# Attenuverting_LinExp_VCA-alt2.net
KiCad netlist of a schematic drawn in EAGLE
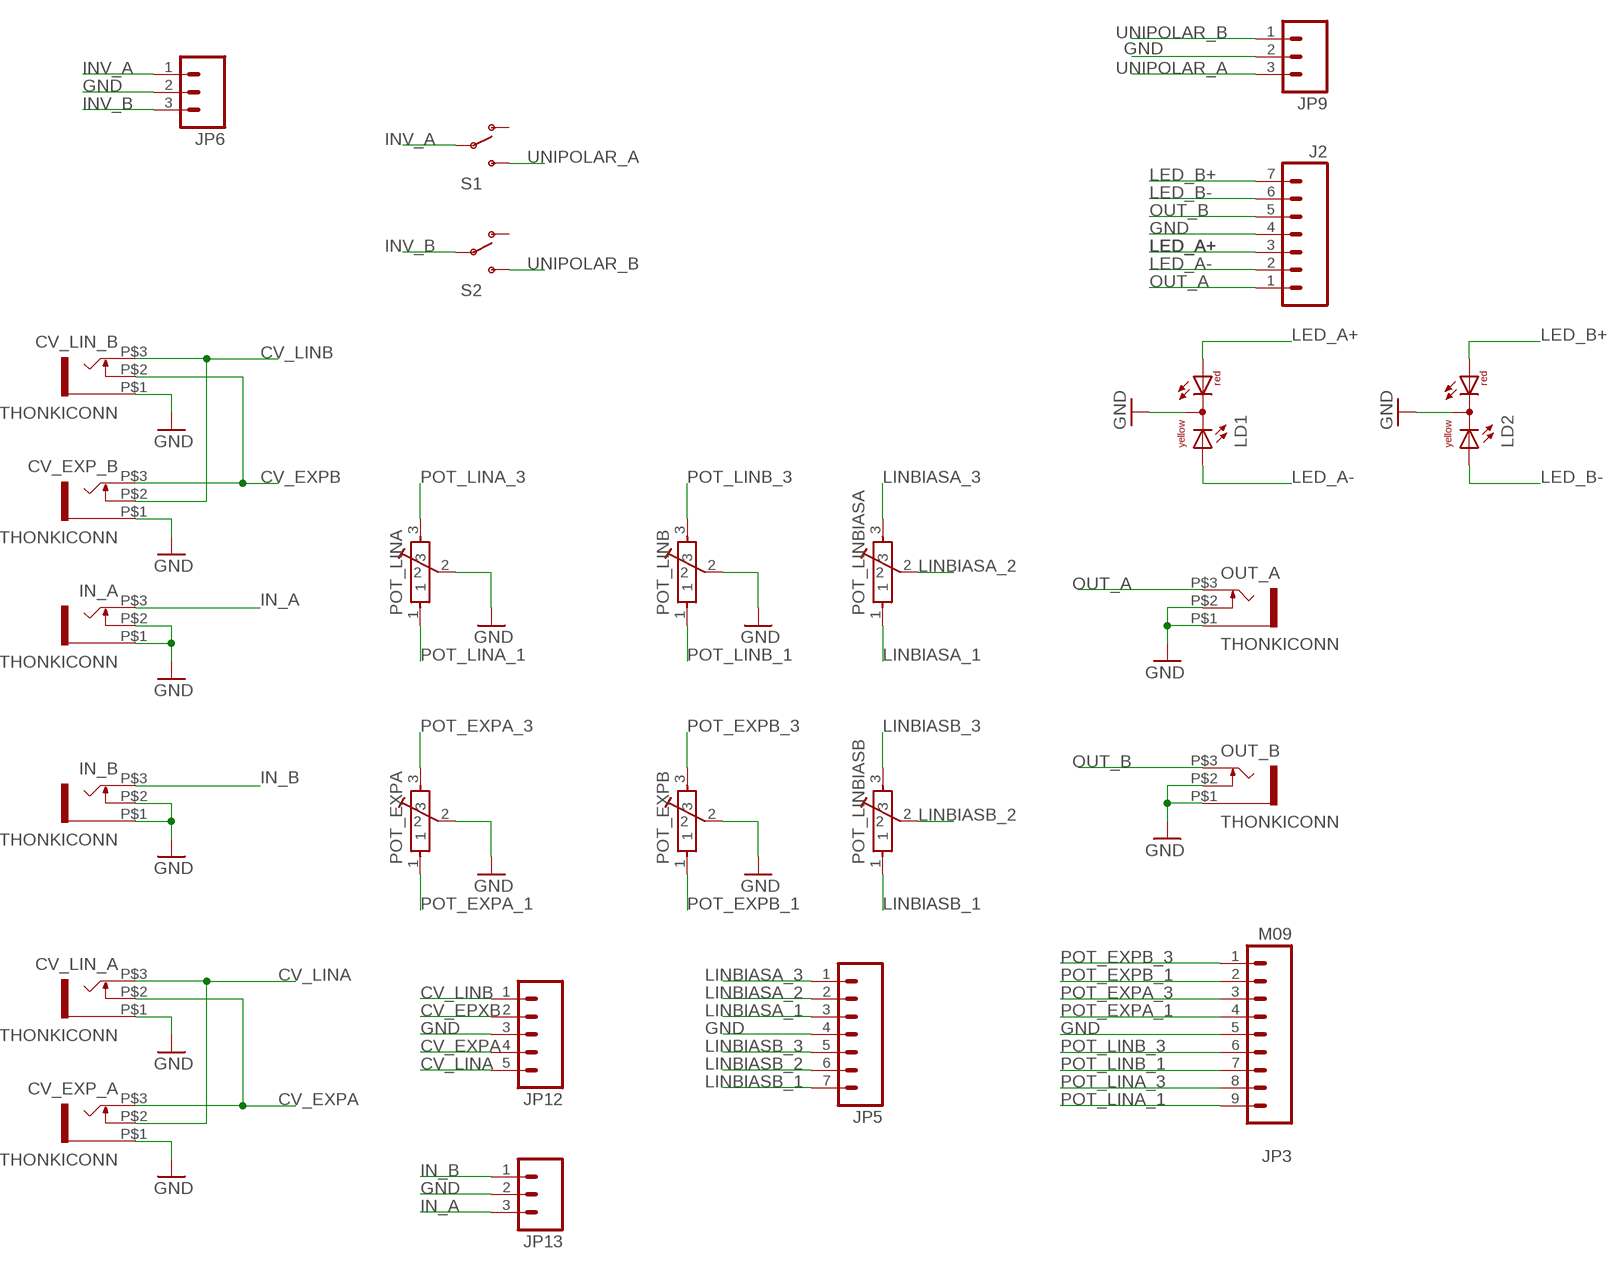
[diagram p0: schematic, sheet 1]
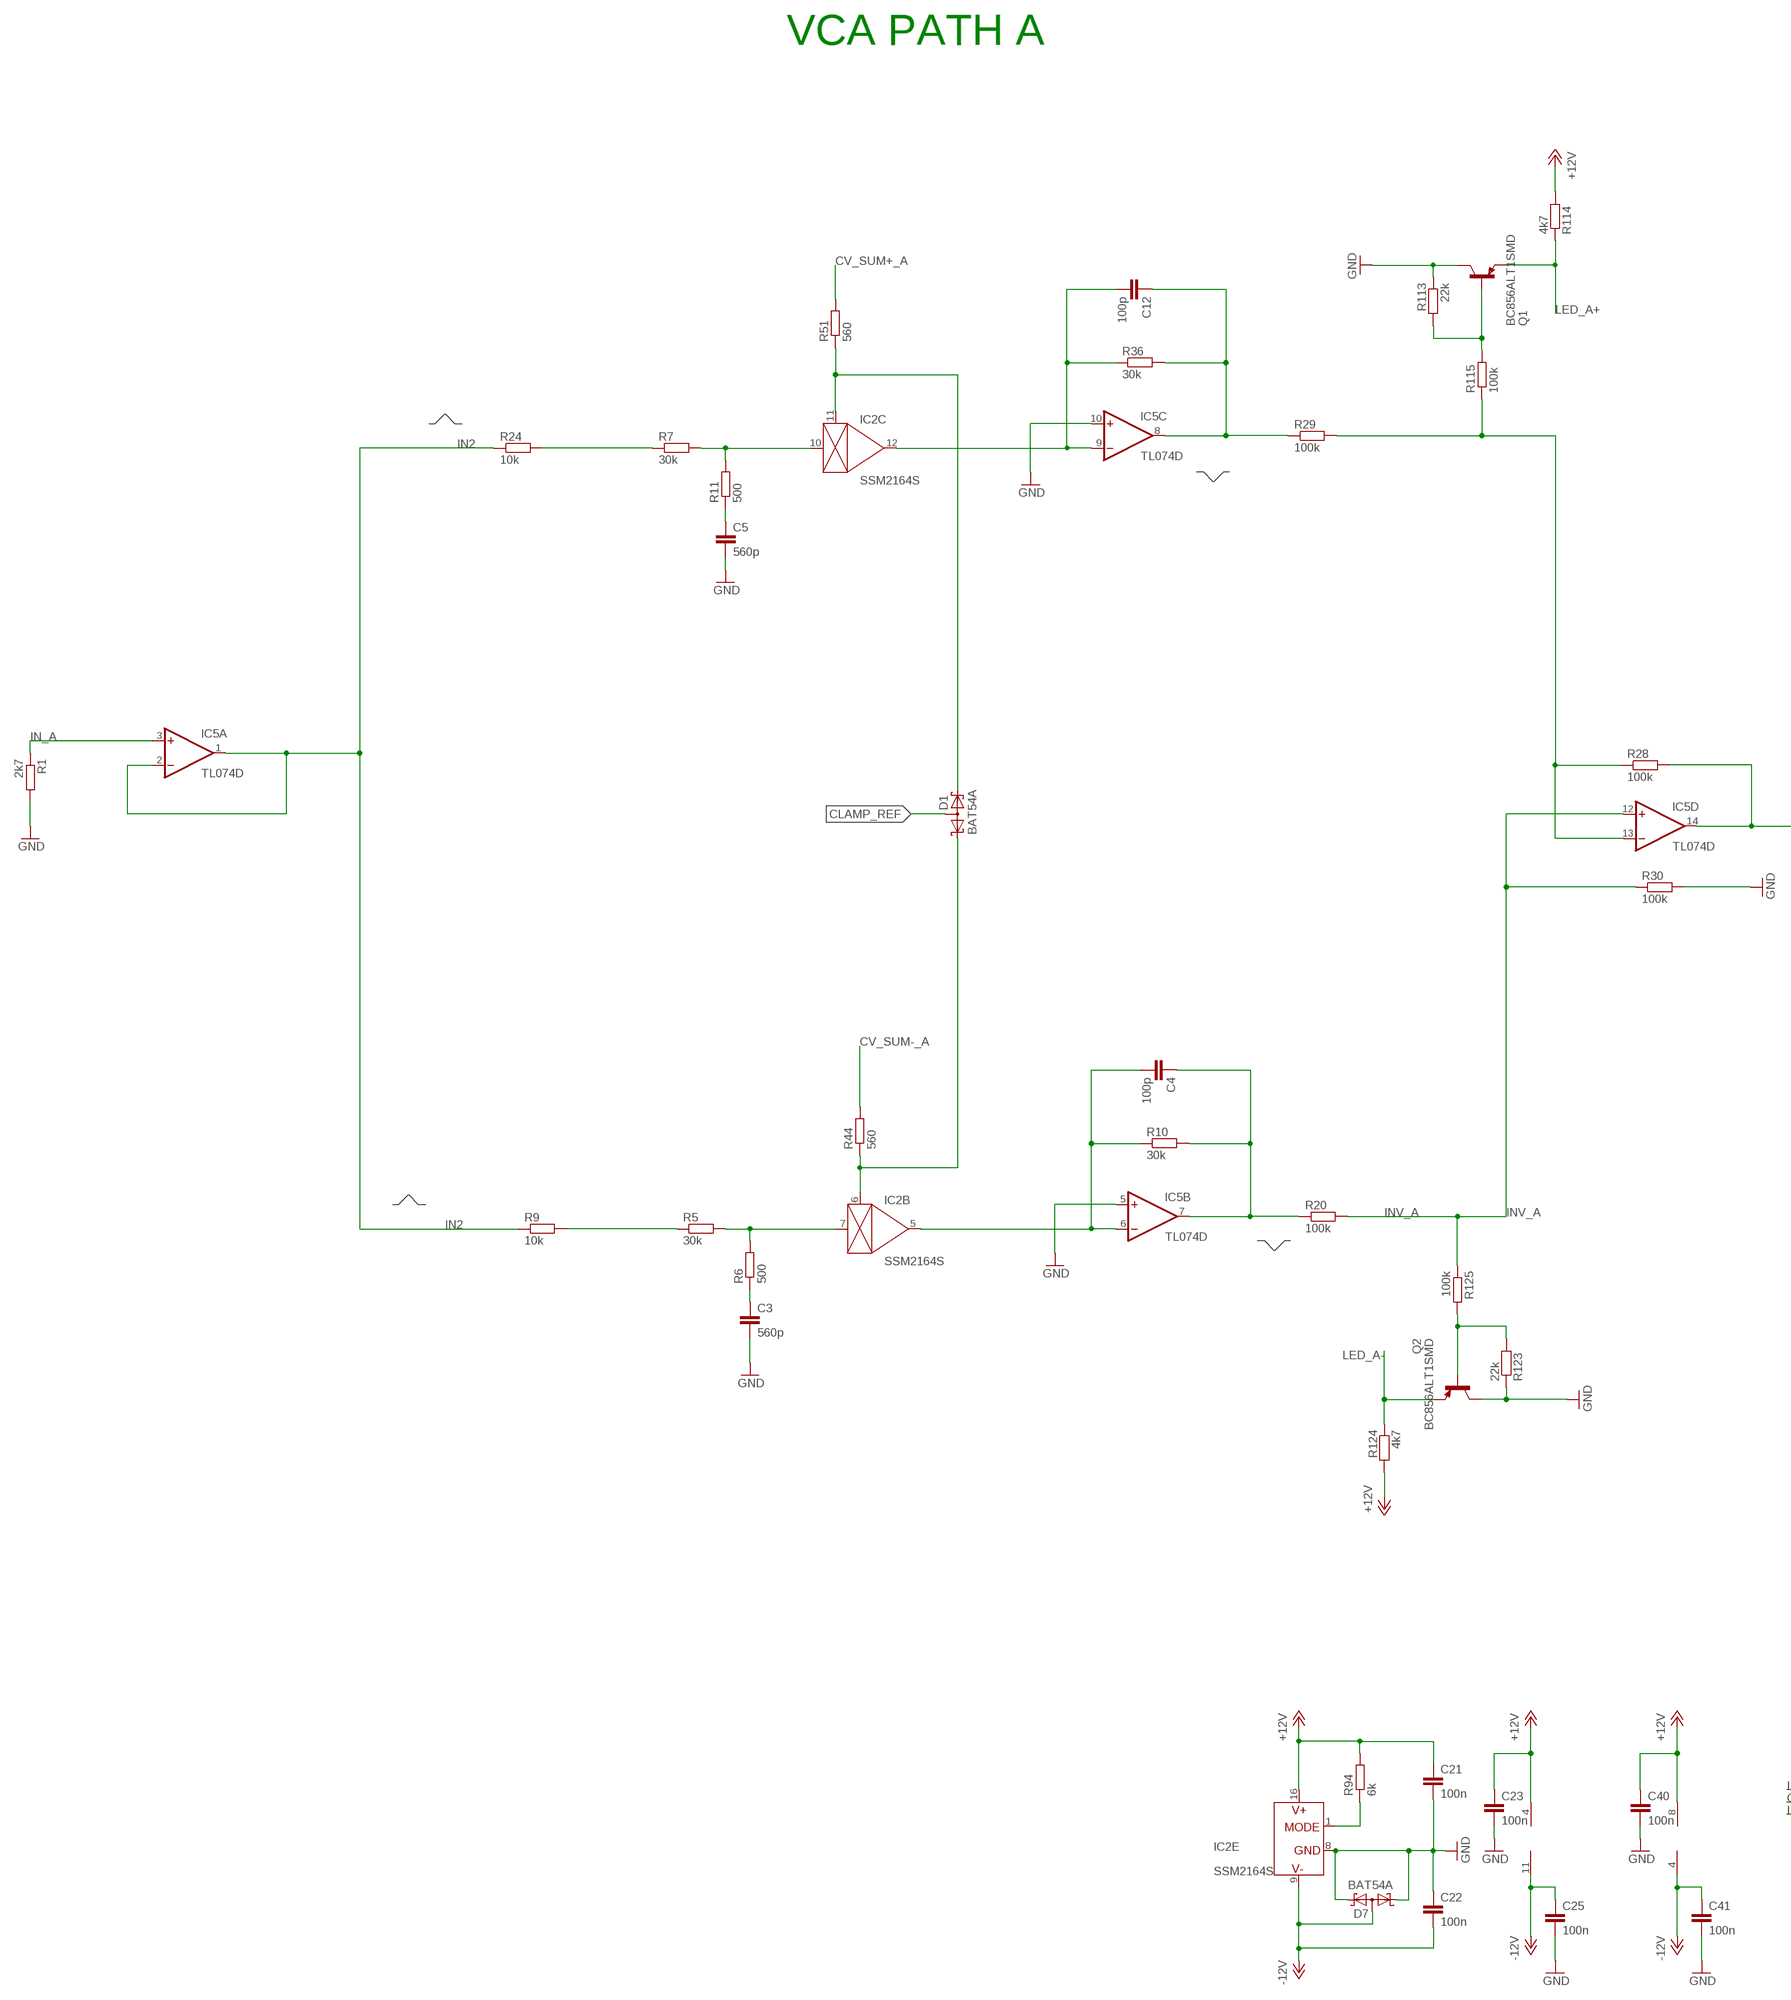
[diagram p1: schematic, sheet 2, part 1 of 2]
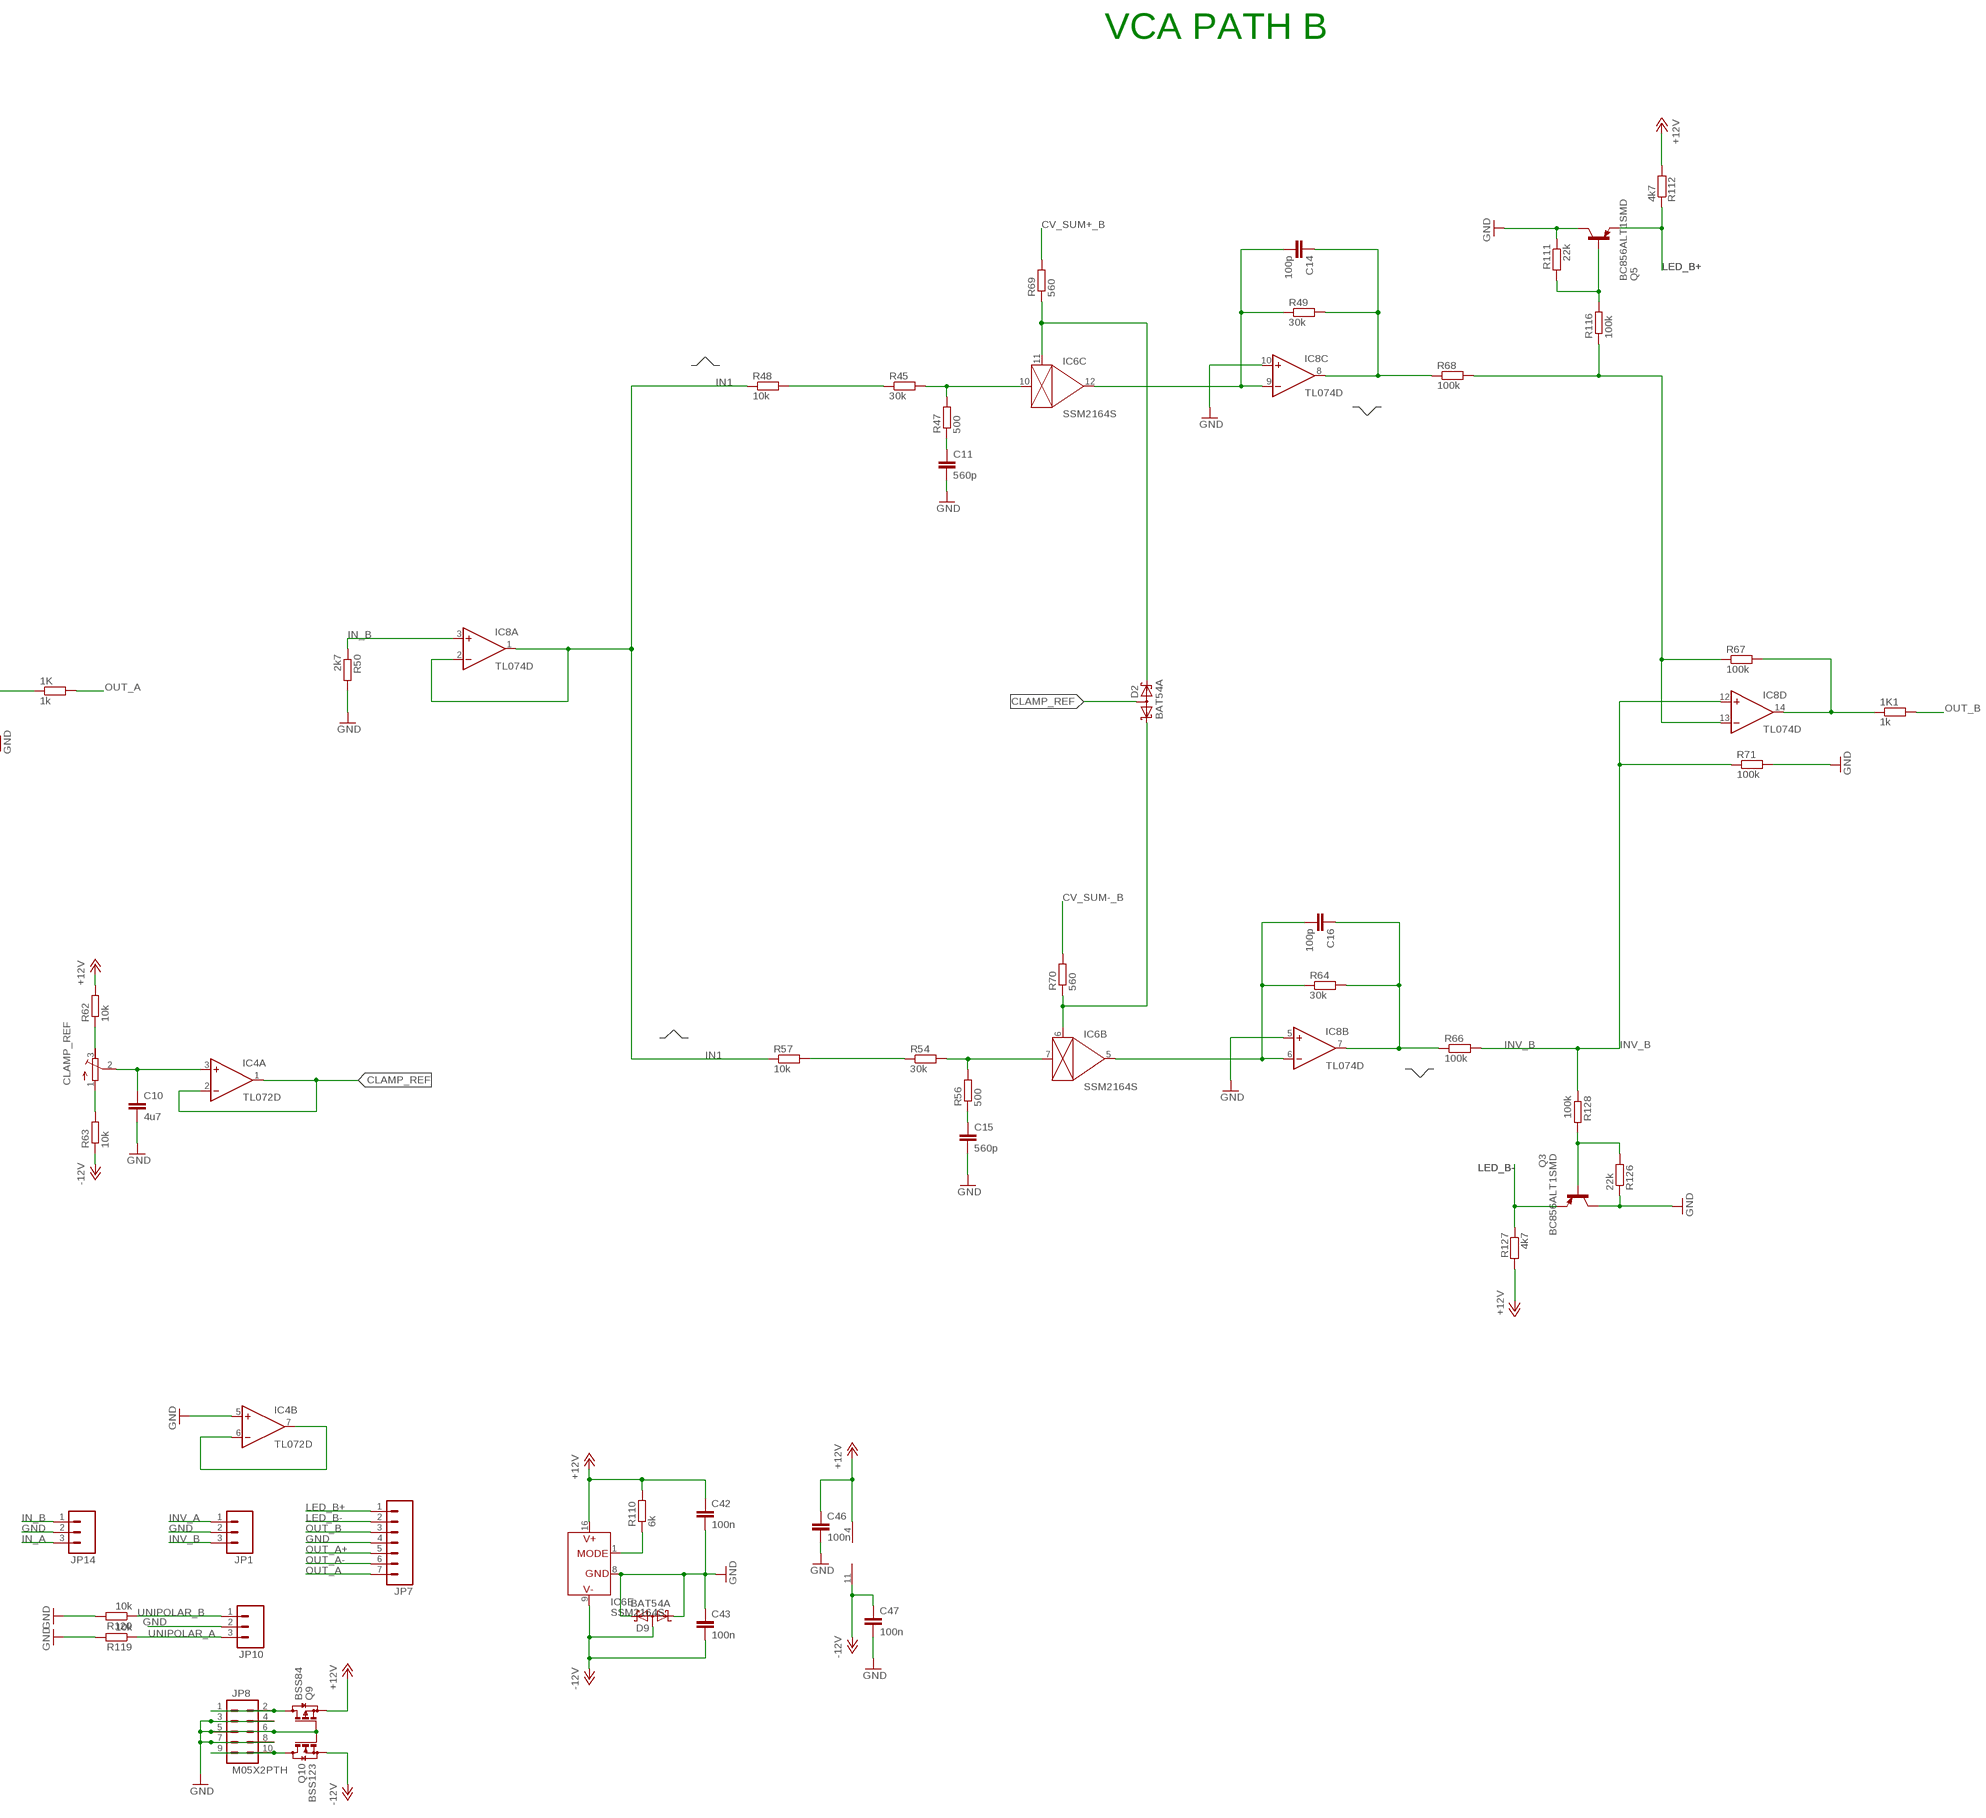
[diagram p2: schematic, sheet 2, part 2 of 2]
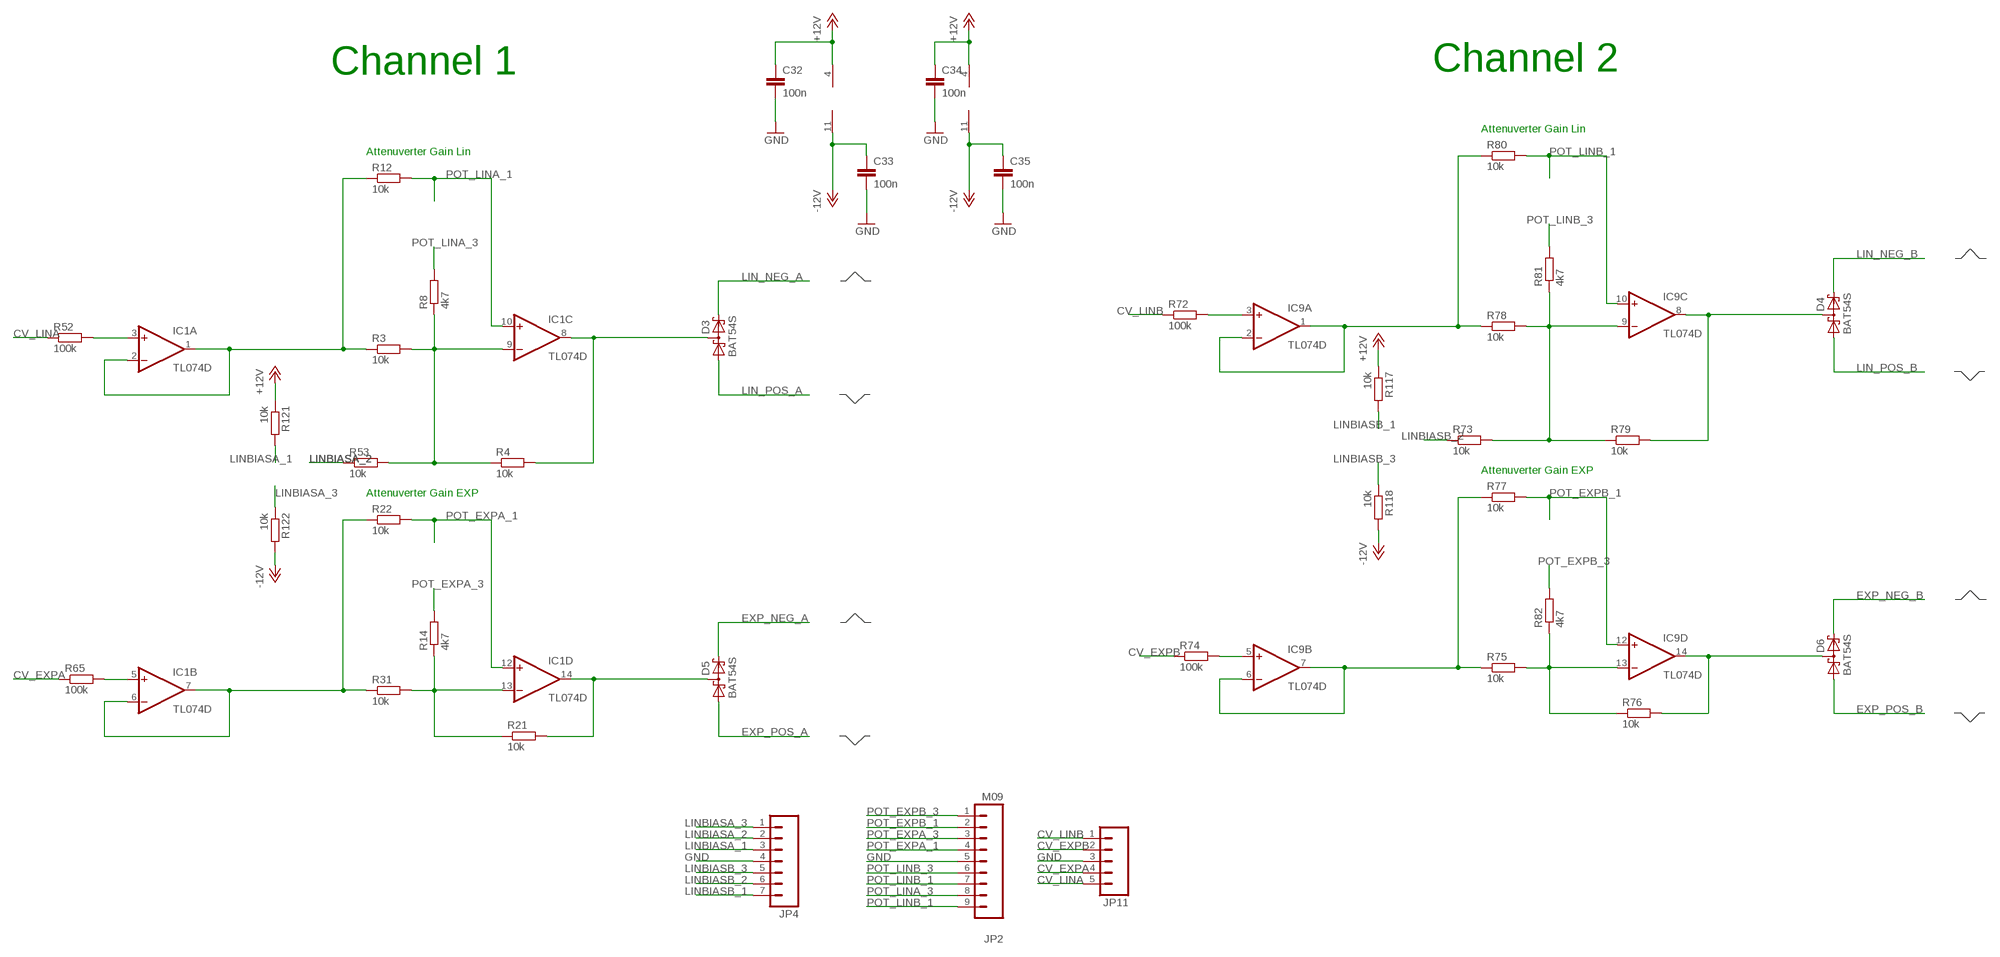
[diagram p3: schematic, sheet 3]
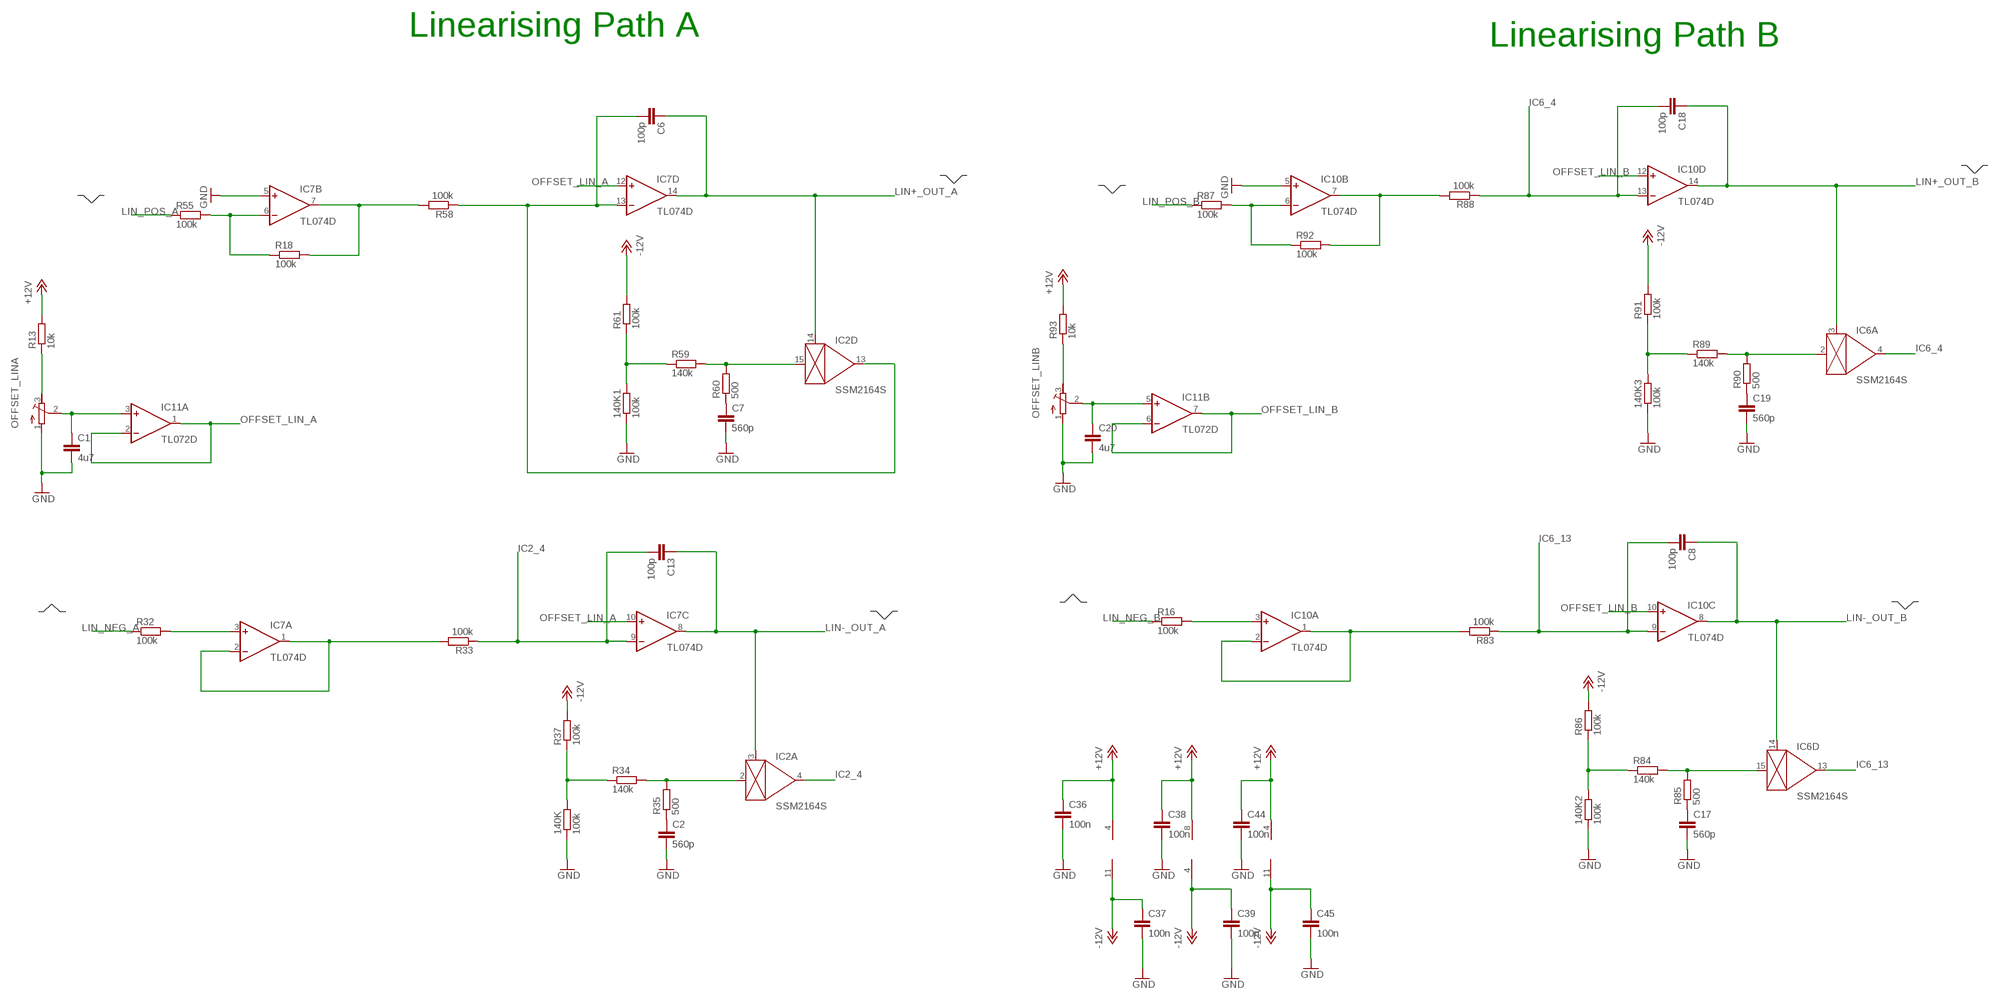
[diagram p4: schematic, sheet 4]
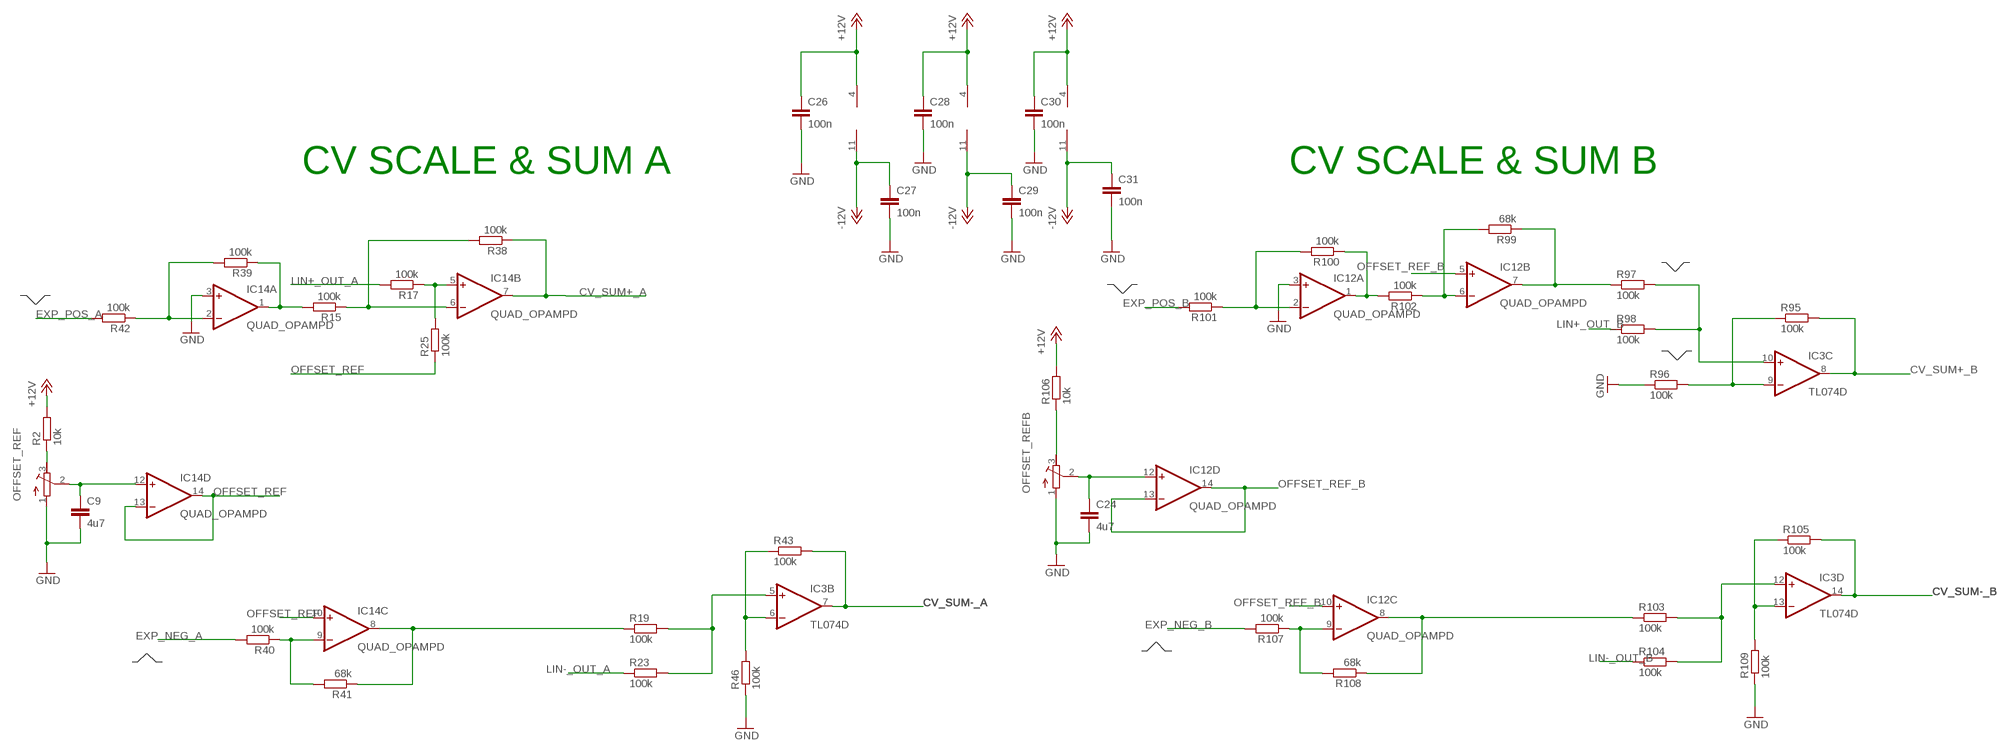
[diagram p5: schematic, sheet 5]

(export (version "E")
  (design (tool "Eeschema 10.0.6"))
  (components
    (comp (ref "140K")
      (value "100k")
      (footprint "eagle-import:0603")
      (libsource (lib "eagle-import") (part "R-EU_0603"))
    )
    (comp (ref "140K1")
      (value "100k")
      (footprint "eagle-import:0603")
      (libsource (lib "eagle-import") (part "R-EU_0603"))
    )
    (comp (ref "140K2")
      (value "100k")
      (footprint "eagle-import:0603")
      (libsource (lib "eagle-import") (part "R-EU_0603"))
    )
    (comp (ref "140K3")
      (value "100k")
      (footprint "eagle-import:0603")
      (libsource (lib "eagle-import") (part "R-EU_0603"))
    )
    (comp (ref "C1")
      (value "4u7")
      (footprint "eagle-import:C0603K")
      (libsource (lib "eagle-import") (part "resistor_C-EUC0603K"))
    )
    (comp (ref "C2")
      (value "560p")
      (footprint "eagle-import:C0603K")
      (libsource (lib "eagle-import") (part "resistor_C-EUC0603K"))
    )
    (comp (ref "C6")
      (value "100p")
      (footprint "eagle-import:C0603K")
      (libsource (lib "eagle-import") (part "resistor_C-EUC0603K"))
    )
    (comp (ref "C7")
      (value "560p")
      (footprint "eagle-import:C0603K")
      (libsource (lib "eagle-import") (part "resistor_C-EUC0603K"))
    )
    (comp (ref "C8")
      (value "100p")
      (footprint "eagle-import:C0603K")
      (libsource (lib "eagle-import") (part "resistor_C-EUC0603K"))
    )
    (comp (ref "C13")
      (value "100p")
      (footprint "eagle-import:C0603K")
      (libsource (lib "eagle-import") (part "resistor_C-EUC0603K"))
    )
    (comp (ref "C17")
      (value "560p")
      (footprint "eagle-import:C0603K")
      (libsource (lib "eagle-import") (part "resistor_C-EUC0603K"))
    )
    (comp (ref "C18")
      (value "100p")
      (footprint "eagle-import:C0603K")
      (libsource (lib "eagle-import") (part "resistor_C-EUC0603K"))
    )
    (comp (ref "C19")
      (value "560p")
      (footprint "eagle-import:C0603K")
      (libsource (lib "eagle-import") (part "resistor_C-EUC0603K"))
    )
    (comp (ref "C20")
      (value "4u7")
      (footprint "eagle-import:C0603K")
      (libsource (lib "eagle-import") (part "resistor_C-EUC0603K"))
    )
    (comp (ref "C36")
      (value "100n")
      (footprint "eagle-import:C0603K")
      (libsource (lib "eagle-import") (part "rcl@1_C-EUC0603K"))
    )
    (comp (ref "C37")
      (value "100n")
      (footprint "eagle-import:C0603K")
      (libsource (lib "eagle-import") (part "rcl@1_C-EUC0603K"))
    )
    (comp (ref "C38")
      (value "100n")
      (footprint "eagle-import:C0603K")
      (libsource (lib "eagle-import") (part "rcl@1_C-EUC0603K"))
    )
    (comp (ref "C39")
      (value "100n")
      (footprint "eagle-import:C0603K")
      (libsource (lib "eagle-import") (part "rcl@1_C-EUC0603K"))
    )
    (comp (ref "C44")
      (value "100n")
      (footprint "eagle-import:C0603K")
      (libsource (lib "eagle-import") (part "rcl@1_C-EUC0603K"))
    )
    (comp (ref "C45")
      (value "100n")
      (footprint "eagle-import:C0603K")
      (libsource (lib "eagle-import") (part "rcl@1_C-EUC0603K"))
    )
    (comp (ref "IC2")
      (value "SSM2164S")
      (footprint "eagle-import:SOIC16N")
      (fields (field (name "OC_FARNELL") "unknown"))
      (libsource (lib "eagle-import") (part "SSM2164S"))
    )
    (comp (ref "IC6")
      (value "SSM2164S")
      (footprint "eagle-import:SOIC16N")
      (fields (field (name "OC_FARNELL") "unknown"))
      (libsource (lib "eagle-import") (part "SSM2164S"))
    )
    (comp (ref "IC7")
      (value "TL074D")
      (footprint "eagle-import:SO14")
      (fields (field (name "OC_FARNELL") "unknown"))
      (libsource (lib "eagle-import") (part "TL074D"))
    )
    (comp (ref "IC10")
      (value "TL074D")
      (footprint "eagle-import:SO14")
      (fields (field (name "OC_FARNELL") "unknown"))
      (libsource (lib "eagle-import") (part "TL074D"))
    )
    (comp (ref "IC11")
      (value "TL072D")
      (footprint "eagle-import:SO08")
      (fields (field (name "OC_FARNELL") "unknown"))
      (libsource (lib "eagle-import") (part "TL072D"))
    )
    (comp (ref "OFFSET_LINA")
      (value "R-TRIMM64W")
      (footprint "eagle-import:RTRIM64W")
      (libsource (lib "eagle-import") (part "R-TRIMM64W"))
    )
    (comp (ref "OFFSET_LINB")
      (value "R-TRIMM64W")
      (footprint "eagle-import:RTRIM64W")
      (libsource (lib "eagle-import") (part "R-TRIMM64W"))
    )
    (comp (ref "R13")
      (value "10k")
      (footprint "eagle-import:0603")
      (libsource (lib "eagle-import") (part "R-EU_0603"))
    )
    (comp (ref "R16")
      (value "100k")
      (footprint "eagle-import:0603")
      (libsource (lib "eagle-import") (part "R-EU_0603"))
    )
    (comp (ref "R18")
      (value "100k")
      (footprint "eagle-import:0603")
      (libsource (lib "eagle-import") (part "R-EU_0603"))
    )
    (comp (ref "R32")
      (value "100k")
      (footprint "eagle-import:0603")
      (libsource (lib "eagle-import") (part "R-EU_0603"))
    )
    (comp (ref "R33")
      (value "100k")
      (footprint "eagle-import:0603")
      (libsource (lib "eagle-import") (part "R-EU_0603"))
    )
    (comp (ref "R34")
      (value "140k")
      (footprint "eagle-import:0603")
      (libsource (lib "eagle-import") (part "R-EU_0603"))
    )
    (comp (ref "R35")
      (value "500")
      (footprint "eagle-import:0603")
      (libsource (lib "eagle-import") (part "R-EU_0603"))
    )
    (comp (ref "R37")
      (value "100k")
      (footprint "eagle-import:0603")
      (libsource (lib "eagle-import") (part "R-EU_0603"))
    )
    (comp (ref "R55")
      (value "100k")
      (footprint "eagle-import:0603")
      (libsource (lib "eagle-import") (part "R-EU_0603"))
    )
    (comp (ref "R58")
      (value "100k")
      (footprint "eagle-import:0603")
      (libsource (lib "eagle-import") (part "R-EU_0603"))
    )
    (comp (ref "R59")
      (value "140k")
      (footprint "eagle-import:0603")
      (libsource (lib "eagle-import") (part "R-EU_0603"))
    )
    (comp (ref "R60")
      (value "500")
      (footprint "eagle-import:0603")
      (libsource (lib "eagle-import") (part "R-EU_0603"))
    )
    (comp (ref "R61")
      (value "100k")
      (footprint "eagle-import:0603")
      (libsource (lib "eagle-import") (part "R-EU_0603"))
    )
    (comp (ref "R83")
      (value "100k")
      (footprint "eagle-import:0603")
      (libsource (lib "eagle-import") (part "R-EU_0603"))
    )
    (comp (ref "R84")
      (value "140k")
      (footprint "eagle-import:0603")
      (libsource (lib "eagle-import") (part "R-EU_0603"))
    )
    (comp (ref "R85")
      (value "500")
      (footprint "eagle-import:0603")
      (libsource (lib "eagle-import") (part "R-EU_0603"))
    )
    (comp (ref "R86")
      (value "100k")
      (footprint "eagle-import:0603")
      (libsource (lib "eagle-import") (part "R-EU_0603"))
    )
    (comp (ref "R87")
      (value "100k")
      (footprint "eagle-import:0603")
      (libsource (lib "eagle-import") (part "R-EU_0603"))
    )
    (comp (ref "R88")
      (value "100k")
      (footprint "eagle-import:0603")
      (libsource (lib "eagle-import") (part "R-EU_0603"))
    )
    (comp (ref "R89")
      (value "140k")
      (footprint "eagle-import:0603")
      (libsource (lib "eagle-import") (part "R-EU_0603"))
    )
    (comp (ref "R90")
      (value "500")
      (footprint "eagle-import:0603")
      (libsource (lib "eagle-import") (part "R-EU_0603"))
    )
    (comp (ref "R91")
      (value "100k")
      (footprint "eagle-import:0603")
      (libsource (lib "eagle-import") (part "R-EU_0603"))
    )
    (comp (ref "R92")
      (value "100k")
      (footprint "eagle-import:0603")
      (libsource (lib "eagle-import") (part "R-EU_0603"))
    )
    (comp (ref "R93")
      (value "10k")
      (footprint "eagle-import:0603")
      (libsource (lib "eagle-import") (part "R-EU_0603"))
    )
    (comp (ref "CV_EXP_A")
      (value "THONKICONN")
      (footprint "eagle-import:THONKICONN")
      (libsource (lib "eagle-import") (part "THONKICONN"))
    )
    (comp (ref "CV_EXP_B")
      (value "THONKICONN")
      (footprint "eagle-import:THONKICONN")
      (libsource (lib "eagle-import") (part "THONKICONN"))
    )
    (comp (ref "CV_LIN_A")
      (value "THONKICONN")
      (footprint "eagle-import:THONKICONN")
      (libsource (lib "eagle-import") (part "THONKICONN"))
    )
    (comp (ref "CV_LIN_B")
      (value "THONKICONN")
      (footprint "eagle-import:THONKICONN")
      (libsource (lib "eagle-import") (part "THONKICONN"))
    )
    (comp (ref "IN_A")
      (value "THONKICONN")
      (footprint "eagle-import:THONKICONN")
      (libsource (lib "eagle-import") (part "THONKICONN"))
    )
    (comp (ref "IN_B")
      (value "THONKICONN")
      (footprint "eagle-import:THONKICONN")
      (libsource (lib "eagle-import") (part "THONKICONN"))
    )
    (comp (ref "J2")
      (value "M07")
      (footprint "eagle-import:1X07")
      (libsource (lib "eagle-import") (part "M07"))
    )
    (comp (ref "JP3")
      (value "M09")
      (footprint "eagle-import:1X09")
      (libsource (lib "eagle-import") (part "M09"))
    )
    (comp (ref "JP5")
      (value "M07")
      (footprint "eagle-import:1X07")
      (libsource (lib "eagle-import") (part "M07"))
    )
    (comp (ref "JP6")
      (value "M03PTH")
      (footprint "eagle-import:1X03")
      (libsource (lib "eagle-import") (part "M03PTH"))
    )
    (comp (ref "JP9")
      (value "M03PTH")
      (footprint "eagle-import:1X03")
      (libsource (lib "eagle-import") (part "M03PTH"))
    )
    (comp (ref "JP12")
      (value "M05PTH")
      (footprint "eagle-import:1X05")
      (libsource (lib "eagle-import") (part "M05PTH"))
    )
    (comp (ref "JP13")
      (value "M03PTH")
      (footprint "eagle-import:1X03")
      (libsource (lib "eagle-import") (part "M03PTH"))
    )
    (comp (ref "LD1")
      (value "DUOLED-RY-C")
      (footprint "eagle-import:DUOLED-C-5MM")
      (libsource (lib "eagle-import") (part "DUOLED-RY-C"))
    )
    (comp (ref "LD2")
      (value "DUOLED-RY-C")
      (footprint "eagle-import:DUOLED-C-5MM")
      (libsource (lib "eagle-import") (part "DUOLED-RY-C"))
    )
    (comp (ref "OUT_A")
      (value "THONKICONN")
      (footprint "eagle-import:THONKICONN")
      (libsource (lib "eagle-import") (part "THONKICONN"))
    )
    (comp (ref "OUT_B")
      (value "THONKICONN")
      (footprint "eagle-import:THONKICONN")
      (libsource (lib "eagle-import") (part "THONKICONN"))
    )
    (comp (ref "POT_EXPA")
      (value "POT-ALPS-RK09L1140")
      (footprint "eagle-import:POT-ALPS-RK09L1140")
      (libsource (lib "eagle-import") (part "POT-ALPS-RK09L1140"))
    )
    (comp (ref "POT_EXPB")
      (value "POT-ALPS-RK09L1140")
      (footprint "eagle-import:POT-ALPS-RK09L1140")
      (libsource (lib "eagle-import") (part "POT-ALPS-RK09L1140"))
    )
    (comp (ref "POT_LINA")
      (value "POT-ALPS-RK09L1140")
      (footprint "eagle-import:POT-ALPS-RK09L1140")
      (libsource (lib "eagle-import") (part "POT-ALPS-RK09L1140"))
    )
    (comp (ref "POT_LINB")
      (value "POT-ALPS-RK09L1140")
      (footprint "eagle-import:POT-ALPS-RK09L1140")
      (libsource (lib "eagle-import") (part "POT-ALPS-RK09L1140"))
    )
    (comp (ref "POT_LINBIASA")
      (value "POT-ALPS-RK09L1140")
      (footprint "eagle-import:POT-ALPS-RK09L1140")
      (libsource (lib "eagle-import") (part "POT-ALPS-RK09L1140"))
    )
    (comp (ref "POT_LINBIASB")
      (value "POT-ALPS-RK09L1140")
      (footprint "eagle-import:POT-ALPS-RK09L1140")
      (libsource (lib "eagle-import") (part "POT-ALPS-RK09L1140"))
    )
    (comp (ref "S1")
      (value "SWITCH-SPST")
      (footprint "eagle-import:SWITCH-SPDT-SALECOM-T8014")
      (libsource (lib "eagle-import") (part "SWITCH-SPST"))
    )
    (comp (ref "S2")
      (value "SWITCH-SPST")
      (footprint "eagle-import:SWITCH-SPDT-SALECOM-T8014")
      (libsource (lib "eagle-import") (part "SWITCH-SPST"))
    )
    (comp (ref "C32")
      (value "100n")
      (footprint "eagle-import:C0603K")
      (libsource (lib "eagle-import") (part "C-EUC0603K"))
    )
    (comp (ref "C33")
      (value "100n")
      (footprint "eagle-import:C0603K")
      (libsource (lib "eagle-import") (part "C-EUC0603K"))
    )
    (comp (ref "C34")
      (value "100n")
      (footprint "eagle-import:C0603K")
      (libsource (lib "eagle-import") (part "C-EUC0603K"))
    )
    (comp (ref "C35")
      (value "100n")
      (footprint "eagle-import:C0603K")
      (libsource (lib "eagle-import") (part "C-EUC0603K"))
    )
    (comp (ref "D3")
      (value "BAT54S")
      (footprint "eagle-import:SOT23")
      (libsource (lib "eagle-import") (part "BAT54S"))
    )
    (comp (ref "D4")
      (value "BAT54S")
      (footprint "eagle-import:SOT23")
      (libsource (lib "eagle-import") (part "BAT54S"))
    )
    (comp (ref "D5")
      (value "BAT54S")
      (footprint "eagle-import:SOT23")
      (libsource (lib "eagle-import") (part "BAT54S"))
    )
    (comp (ref "D6")
      (value "BAT54S")
      (footprint "eagle-import:SOT23")
      (libsource (lib "eagle-import") (part "BAT54S"))
    )
    (comp (ref "IC1")
      (value "TL074D")
      (footprint "eagle-import:SO14")
      (fields (field (name "OC_FARNELL") "unknown"))
      (libsource (lib "eagle-import") (part "TL074D"))
    )
    (comp (ref "IC9")
      (value "TL074D")
      (footprint "eagle-import:SO14")
      (fields (field (name "OC_FARNELL") "unknown"))
      (libsource (lib "eagle-import") (part "TL074D"))
    )
    (comp (ref "JP2")
      (value "M09")
      (footprint "eagle-import:1X09")
      (libsource (lib "eagle-import") (part "M09"))
    )
    (comp (ref "JP4")
      (value "M07")
      (footprint "eagle-import:1X07")
      (libsource (lib "eagle-import") (part "M07"))
    )
    (comp (ref "JP11")
      (value "M05PTH")
      (footprint "eagle-import:1X05")
      (libsource (lib "eagle-import") (part "M05PTH"))
    )
    (comp (ref "R3")
      (value "10k")
      (footprint "eagle-import:0603")
      (libsource (lib "eagle-import") (part "R-EU_0603"))
    )
    (comp (ref "R4")
      (value "10k")
      (footprint "eagle-import:0603")
      (libsource (lib "eagle-import") (part "R-EU_0603"))
    )
    (comp (ref "R8")
      (value "4k7")
      (footprint "eagle-import:0603")
      (libsource (lib "eagle-import") (part "R-EU_0603"))
    )
    (comp (ref "R12")
      (value "10k")
      (footprint "eagle-import:0603")
      (libsource (lib "eagle-import") (part "R-EU_0603"))
    )
    (comp (ref "R14")
      (value "4k7")
      (footprint "eagle-import:0603")
      (libsource (lib "eagle-import") (part "R-EU_0603"))
    )
    (comp (ref "R21")
      (value "10k")
      (footprint "eagle-import:0603")
      (libsource (lib "eagle-import") (part "R-EU_0603"))
    )
    (comp (ref "R22")
      (value "10k")
      (footprint "eagle-import:0603")
      (libsource (lib "eagle-import") (part "R-EU_0603"))
    )
    (comp (ref "R31")
      (value "10k")
      (footprint "eagle-import:0603")
      (libsource (lib "eagle-import") (part "R-EU_0603"))
    )
    (comp (ref "R52")
      (value "100k")
      (footprint "eagle-import:0603")
      (libsource (lib "eagle-import") (part "R-EU_0603"))
    )
    (comp (ref "R53")
      (value "10k")
      (footprint "eagle-import:0603")
      (libsource (lib "eagle-import") (part "R-EU_0603"))
    )
    (comp (ref "R65")
      (value "100k")
      (footprint "eagle-import:0603")
      (libsource (lib "eagle-import") (part "R-EU_0603"))
    )
    (comp (ref "R72")
      (value "100k")
      (footprint "eagle-import:0603")
      (libsource (lib "eagle-import") (part "R-EU_0603"))
    )
    (comp (ref "R73")
      (value "10k")
      (footprint "eagle-import:0603")
      (libsource (lib "eagle-import") (part "R-EU_0603"))
    )
    (comp (ref "R74")
      (value "100k")
      (footprint "eagle-import:0603")
      (libsource (lib "eagle-import") (part "R-EU_0603"))
    )
    (comp (ref "R75")
      (value "10k")
      (footprint "eagle-import:0603")
      (libsource (lib "eagle-import") (part "R-EU_0603"))
    )
    (comp (ref "R76")
      (value "10k")
      (footprint "eagle-import:0603")
      (libsource (lib "eagle-import") (part "R-EU_0603"))
    )
    (comp (ref "R77")
      (value "10k")
      (footprint "eagle-import:0603")
      (libsource (lib "eagle-import") (part "R-EU_0603"))
    )
    (comp (ref "R78")
      (value "10k")
      (footprint "eagle-import:0603")
      (libsource (lib "eagle-import") (part "R-EU_0603"))
    )
    (comp (ref "R79")
      (value "10k")
      (footprint "eagle-import:0603")
      (libsource (lib "eagle-import") (part "R-EU_0603"))
    )
    (comp (ref "R80")
      (value "10k")
      (footprint "eagle-import:0603")
      (libsource (lib "eagle-import") (part "R-EU_0603"))
    )
    (comp (ref "R81")
      (value "4k7")
      (footprint "eagle-import:0603")
      (libsource (lib "eagle-import") (part "R-EU_0603"))
    )
    (comp (ref "R82")
      (value "4k7")
      (footprint "eagle-import:0603")
      (libsource (lib "eagle-import") (part "R-EU_0603"))
    )
    (comp (ref "R117")
      (value "10k")
      (footprint "eagle-import:0603")
      (libsource (lib "eagle-import") (part "R-EU_0603"))
    )
    (comp (ref "R118")
      (value "10k")
      (footprint "eagle-import:0603")
      (libsource (lib "eagle-import") (part "R-EU_0603"))
    )
    (comp (ref "R121")
      (value "10k")
      (footprint "eagle-import:0603")
      (libsource (lib "eagle-import") (part "R-EU_0603"))
    )
    (comp (ref "R122")
      (value "10k")
      (footprint "eagle-import:0603")
      (libsource (lib "eagle-import") (part "R-EU_0603"))
    )
    (comp (ref "1K")
      (value "1k")
      (footprint "eagle-import:0603")
      (fields (field (name "MF") "MULTICOMP") (field (name "MPN") "MC0063W06031160K"))
      (libsource (lib "eagle-import") (part "R-EU_0603"))
    )
    (comp (ref "1K1")
      (value "1k")
      (footprint "eagle-import:0603")
      (fields (field (name "MF") "MULTICOMP") (field (name "MPN") "MC0063W06031160K"))
      (libsource (lib "eagle-import") (part "R-EU_0603"))
    )
    (comp (ref "C3")
      (value "560p")
      (footprint "eagle-import:C0603K")
      (libsource (lib "eagle-import") (part "resistor_C-EUC0603K"))
    )
    (comp (ref "C4")
      (value "100p")
      (footprint "eagle-import:C0603K")
      (libsource (lib "eagle-import") (part "resistor_C-EUC0603K"))
    )
    (comp (ref "C5")
      (value "560p")
      (footprint "eagle-import:C0603K")
      (libsource (lib "eagle-import") (part "resistor_C-EUC0603K"))
    )
    (comp (ref "C10")
      (value "4u7")
      (footprint "eagle-import:C0603K")
      (libsource (lib "eagle-import") (part "resistor_C-EUC0603K"))
    )
    (comp (ref "C11")
      (value "560p")
      (footprint "eagle-import:C0603K")
      (libsource (lib "eagle-import") (part "resistor_C-EUC0603K"))
    )
    (comp (ref "C12")
      (value "100p")
      (footprint "eagle-import:C0603K")
      (libsource (lib "eagle-import") (part "resistor_C-EUC0603K"))
    )
    (comp (ref "C14")
      (value "100p")
      (footprint "eagle-import:C0603K")
      (libsource (lib "eagle-import") (part "resistor_C-EUC0603K"))
    )
    (comp (ref "C15")
      (value "560p")
      (footprint "eagle-import:C0603K")
      (libsource (lib "eagle-import") (part "resistor_C-EUC0603K"))
    )
    (comp (ref "C16")
      (value "100p")
      (footprint "eagle-import:C0603K")
      (libsource (lib "eagle-import") (part "resistor_C-EUC0603K"))
    )
    (comp (ref "C21")
      (value "100n")
      (footprint "eagle-import:C0603K")
      (libsource (lib "eagle-import") (part "C-EUC0603K"))
    )
    (comp (ref "C22")
      (value "100n")
      (footprint "eagle-import:C0603K")
      (libsource (lib "eagle-import") (part "C-EUC0603K"))
    )
    (comp (ref "C23")
      (value "100n")
      (footprint "eagle-import:C0603K")
      (libsource (lib "eagle-import") (part "C-EUC0603K"))
    )
    (comp (ref "C25")
      (value "100n")
      (footprint "eagle-import:C0603K")
      (libsource (lib "eagle-import") (part "C-EUC0603K"))
    )
    (comp (ref "C40")
      (value "100n")
      (footprint "eagle-import:C0603K")
      (libsource (lib "eagle-import") (part "C-EUC0603K"))
    )
    (comp (ref "C41")
      (value "100n")
      (footprint "eagle-import:C0603K")
      (libsource (lib "eagle-import") (part "C-EUC0603K"))
    )
    (comp (ref "C42")
      (value "100n")
      (footprint "eagle-import:C0603K")
      (libsource (lib "eagle-import") (part "C-EUC0603K"))
    )
    (comp (ref "C43")
      (value "100n")
      (footprint "eagle-import:C0603K")
      (libsource (lib "eagle-import") (part "C-EUC0603K"))
    )
    (comp (ref "C46")
      (value "100n")
      (footprint "eagle-import:C0603K")
      (libsource (lib "eagle-import") (part "C-EUC0603K"))
    )
    (comp (ref "C47")
      (value "100n")
      (footprint "eagle-import:C0603K")
      (libsource (lib "eagle-import") (part "C-EUC0603K"))
    )
    (comp (ref "CLAMP_REF")
      (value "R-TRIMM64W")
      (footprint "eagle-import:RTRIM64W")
      (libsource (lib "eagle-import") (part "R-TRIMM64W"))
    )
    (comp (ref "D1")
      (value "BAT54A")
      (footprint "eagle-import:SOT23")
      (libsource (lib "eagle-import") (part "BAT54A"))
    )
    (comp (ref "D2")
      (value "BAT54A")
      (footprint "eagle-import:SOT23")
      (libsource (lib "eagle-import") (part "BAT54A"))
    )
    (comp (ref "D7")
      (value "BAT54A")
      (footprint "eagle-import:SOT23")
      (libsource (lib "eagle-import") (part "BAT54A"))
    )
    (comp (ref "D9")
      (value "BAT54A")
      (footprint "eagle-import:SOT23")
      (libsource (lib "eagle-import") (part "BAT54A"))
    )
    (comp (ref "IC4")
      (value "TL072D")
      (footprint "eagle-import:SO08")
      (libsource (lib "eagle-import") (part "TL072D"))
    )
    (comp (ref "IC5")
      (value "TL074D")
      (footprint "eagle-import:SO14")
      (fields (field (name "OC_FARNELL") "unknown"))
      (libsource (lib "eagle-import") (part "TL074D"))
    )
    (comp (ref "IC8")
      (value "TL074D")
      (footprint "eagle-import:SO14")
      (fields (field (name "OC_FARNELL") "unknown"))
      (libsource (lib "eagle-import") (part "TL074D"))
    )
    (comp (ref "JP1")
      (value "M03PTH")
      (footprint "eagle-import:1X03")
      (libsource (lib "eagle-import") (part "M03PTH"))
    )
    (comp (ref "JP7")
      (value "M07")
      (footprint "eagle-import:1X07")
      (libsource (lib "eagle-import") (part "M07"))
    )
    (comp (ref "JP8")
      (value "M05X2PTH")
      (footprint "eagle-import:AVR_ICSP")
      (libsource (lib "eagle-import") (part "M05X2PTH"))
    )
    (comp (ref "JP10")
      (value "M03PTH")
      (footprint "eagle-import:1X03")
      (libsource (lib "eagle-import") (part "M03PTH"))
    )
    (comp (ref "JP14")
      (value "M03PTH")
      (footprint "eagle-import:1X03")
      (libsource (lib "eagle-import") (part "M03PTH"))
    )
    (comp (ref "Q1")
      (value "BC856ALT1SMD")
      (footprint "eagle-import:SOT23-BEC")
      (libsource (lib "eagle-import") (part "BC856SMDALT1"))
    )
    (comp (ref "Q2")
      (value "BC856ALT1SMD")
      (footprint "eagle-import:SOT23-BEC")
      (libsource (lib "eagle-import") (part "BC856SMDALT1"))
    )
    (comp (ref "Q3")
      (value "BC856ALT1SMD")
      (footprint "eagle-import:SOT23-BEC")
      (libsource (lib "eagle-import") (part "BC856SMDALT1"))
    )
    (comp (ref "Q5")
      (value "BC856ALT1SMD")
      (footprint "eagle-import:SOT23-BEC")
      (libsource (lib "eagle-import") (part "BC856SMDALT1"))
    )
    (comp (ref "Q9")
      (value "BSS84")
      (footprint "eagle-import:SOT23")
      (libsource (lib "eagle-import") (part "BSS84"))
    )
    (comp (ref "Q10")
      (value "BSS123")
      (footprint "eagle-import:SOT23")
      (libsource (lib "eagle-import") (part "BSS123"))
    )
    (comp (ref "R1")
      (value "2k7")
      (footprint "eagle-import:0603")
      (libsource (lib "eagle-import") (part "R-EU_0603"))
    )
    (comp (ref "R5")
      (value "30k")
      (footprint "eagle-import:0603")
      (libsource (lib "eagle-import") (part "R-EU_0603"))
    )
    (comp (ref "R6")
      (value "500")
      (footprint "eagle-import:0603")
      (libsource (lib "eagle-import") (part "R-EU_0603"))
    )
    (comp (ref "R7")
      (value "30k")
      (footprint "eagle-import:0603")
      (libsource (lib "eagle-import") (part "R-EU_0603"))
    )
    (comp (ref "R9")
      (value "10k")
      (footprint "eagle-import:0603")
      (libsource (lib "eagle-import") (part "R-EU_0603"))
    )
    (comp (ref "R10")
      (value "30k")
      (footprint "eagle-import:0603")
      (libsource (lib "eagle-import") (part "R-EU_0603"))
    )
    (comp (ref "R11")
      (value "500")
      (footprint "eagle-import:0603")
      (libsource (lib "eagle-import") (part "R-EU_0603"))
    )
    (comp (ref "R20")
      (value "100k")
      (footprint "eagle-import:0603")
      (libsource (lib "eagle-import") (part "R-EU_0603"))
    )
    (comp (ref "R24")
      (value "10k")
      (footprint "eagle-import:0603")
      (libsource (lib "eagle-import") (part "R-EU_0603"))
    )
    (comp (ref "R28")
      (value "100k")
      (footprint "eagle-import:0603")
      (libsource (lib "eagle-import") (part "R-EU_0603"))
    )
    (comp (ref "R29")
      (value "100k")
      (footprint "eagle-import:0603")
      (libsource (lib "eagle-import") (part "R-EU_0603"))
    )
    (comp (ref "R30")
      (value "100k")
      (footprint "eagle-import:0603")
      (libsource (lib "eagle-import") (part "R-EU_0603"))
    )
    (comp (ref "R36")
      (value "30k")
      (footprint "eagle-import:0603")
      (libsource (lib "eagle-import") (part "R-EU_0603"))
    )
    (comp (ref "R44")
      (value "560")
      (footprint "eagle-import:0603")
      (libsource (lib "eagle-import") (part "R-EU_0603"))
    )
    (comp (ref "R45")
      (value "30k")
      (footprint "eagle-import:0603")
      (libsource (lib "eagle-import") (part "R-EU_0603"))
    )
    (comp (ref "R47")
      (value "500")
      (footprint "eagle-import:0603")
      (libsource (lib "eagle-import") (part "R-EU_0603"))
    )
    (comp (ref "R48")
      (value "10k")
      (footprint "eagle-import:0603")
      (libsource (lib "eagle-import") (part "R-EU_0603"))
    )
    (comp (ref "R49")
      (value "30k")
      (footprint "eagle-import:0603")
      (libsource (lib "eagle-import") (part "R-EU_0603"))
    )
    (comp (ref "R50")
      (value "2k7")
      (footprint "eagle-import:0603")
      (libsource (lib "eagle-import") (part "R-EU_0603"))
    )
    (comp (ref "R51")
      (value "560")
      (footprint "eagle-import:0603")
      (libsource (lib "eagle-import") (part "R-EU_0603"))
    )
    (comp (ref "R54")
      (value "30k")
      (footprint "eagle-import:0603")
      (libsource (lib "eagle-import") (part "R-EU_0603"))
    )
    (comp (ref "R56")
      (value "500")
      (footprint "eagle-import:0603")
      (libsource (lib "eagle-import") (part "R-EU_0603"))
    )
    (comp (ref "R57")
      (value "10k")
      (footprint "eagle-import:0603")
      (libsource (lib "eagle-import") (part "R-EU_0603"))
    )
    (comp (ref "R62")
      (value "10k")
      (footprint "eagle-import:0603")
      (libsource (lib "eagle-import") (part "R-EU_0603"))
    )
    (comp (ref "R63")
      (value "10k")
      (footprint "eagle-import:0603")
      (libsource (lib "eagle-import") (part "R-EU_0603"))
    )
    (comp (ref "R64")
      (value "30k")
      (footprint "eagle-import:0603")
      (libsource (lib "eagle-import") (part "R-EU_0603"))
    )
    (comp (ref "R66")
      (value "100k")
      (footprint "eagle-import:0603")
      (libsource (lib "eagle-import") (part "R-EU_0603"))
    )
    (comp (ref "R67")
      (value "100k")
      (footprint "eagle-import:0603")
      (libsource (lib "eagle-import") (part "R-EU_0603"))
    )
    (comp (ref "R68")
      (value "100k")
      (footprint "eagle-import:0603")
      (libsource (lib "eagle-import") (part "R-EU_0603"))
    )
    (comp (ref "R69")
      (value "560")
      (footprint "eagle-import:0603")
      (libsource (lib "eagle-import") (part "R-EU_0603"))
    )
    (comp (ref "R70")
      (value "560")
      (footprint "eagle-import:0603")
      (libsource (lib "eagle-import") (part "R-EU_0603"))
    )
    (comp (ref "R71")
      (value "100k")
      (footprint "eagle-import:0603")
      (libsource (lib "eagle-import") (part "R-EU_0603"))
    )
    (comp (ref "R94")
      (value "6k")
      (footprint "eagle-import:0603")
      (libsource (lib "eagle-import") (part "R-EU_0603"))
    )
    (comp (ref "R110")
      (value "6k")
      (footprint "eagle-import:0603")
      (libsource (lib "eagle-import") (part "R-EU_0603"))
    )
    (comp (ref "R111")
      (value "22k")
      (footprint "eagle-import:0603")
      (libsource (lib "eagle-import") (part "R-EU_0603"))
    )
    (comp (ref "R112")
      (value "4k7")
      (footprint "eagle-import:0603")
      (libsource (lib "eagle-import") (part "R-EU_0603"))
    )
    (comp (ref "R113")
      (value "22k")
      (footprint "eagle-import:0603")
      (libsource (lib "eagle-import") (part "R-EU_0603"))
    )
    (comp (ref "R114")
      (value "4k7")
      (footprint "eagle-import:0603")
      (libsource (lib "eagle-import") (part "R-EU_0603"))
    )
    (comp (ref "R115")
      (value "100k")
      (footprint "eagle-import:0603")
      (libsource (lib "eagle-import") (part "R-EU_0603"))
    )
    (comp (ref "R116")
      (value "100k")
      (footprint "eagle-import:0603")
      (libsource (lib "eagle-import") (part "R-EU_0603"))
    )
    (comp (ref "R119")
      (value "10k")
      (footprint "eagle-import:0603")
      (libsource (lib "eagle-import") (part "R-EU_0603"))
    )
    (comp (ref "R120")
      (value "10k")
      (footprint "eagle-import:0603")
      (libsource (lib "eagle-import") (part "R-EU_0603"))
    )
    (comp (ref "R123")
      (value "22k")
      (footprint "eagle-import:0603")
      (libsource (lib "eagle-import") (part "R-EU_0603"))
    )
    (comp (ref "R124")
      (value "4k7")
      (footprint "eagle-import:0603")
      (libsource (lib "eagle-import") (part "R-EU_0603"))
    )
    (comp (ref "R125")
      (value "100k")
      (footprint "eagle-import:0603")
      (libsource (lib "eagle-import") (part "R-EU_0603"))
    )
    (comp (ref "R126")
      (value "22k")
      (footprint "eagle-import:0603")
      (libsource (lib "eagle-import") (part "R-EU_0603"))
    )
    (comp (ref "R127")
      (value "4k7")
      (footprint "eagle-import:0603")
      (libsource (lib "eagle-import") (part "R-EU_0603"))
    )
    (comp (ref "R128")
      (value "100k")
      (footprint "eagle-import:0603")
      (libsource (lib "eagle-import") (part "R-EU_0603"))
    )
    (comp (ref "C9")
      (value "4u7")
      (footprint "eagle-import:C0603K")
      (libsource (lib "eagle-import") (part "resistor_C-EUC0603K"))
    )
    (comp (ref "C24")
      (value "4u7")
      (footprint "eagle-import:C0603K")
      (libsource (lib "eagle-import") (part "resistor_C-EUC0603K"))
    )
    (comp (ref "C26")
      (value "100n")
      (footprint "eagle-import:C0603K")
      (libsource (lib "eagle-import") (part "C-EUC0603K"))
    )
    (comp (ref "C27")
      (value "100n")
      (footprint "eagle-import:C0603K")
      (libsource (lib "eagle-import") (part "C-EUC0603K"))
    )
    (comp (ref "C28")
      (value "100n")
      (footprint "eagle-import:C0603K")
      (libsource (lib "eagle-import") (part "C-EUC0603K"))
    )
    (comp (ref "C29")
      (value "100n")
      (footprint "eagle-import:C0603K")
      (libsource (lib "eagle-import") (part "C-EUC0603K"))
    )
    (comp (ref "C30")
      (value "100n")
      (footprint "eagle-import:C0603K")
      (libsource (lib "eagle-import") (part "C-EUC0603K"))
    )
    (comp (ref "C31")
      (value "100n")
      (footprint "eagle-import:C0603K")
      (libsource (lib "eagle-import") (part "C-EUC0603K"))
    )
    (comp (ref "IC3")
      (value "TL074D")
      (footprint "eagle-import:SO14")
      (libsource (lib "eagle-import") (part "TL074D"))
    )
    (comp (ref "IC12")
      (value "QUAD_OPAMPD")
      (footprint "eagle-import:SO14")
      (libsource (lib "eagle-import") (part "QUAD_OPAMPD"))
    )
    (comp (ref "IC14")
      (value "QUAD_OPAMPD")
      (footprint "eagle-import:SO14")
      (libsource (lib "eagle-import") (part "QUAD_OPAMPD"))
    )
    (comp (ref "OFFSET_REF")
      (value "R-TRIMM64W")
      (footprint "eagle-import:RTRIM64W")
      (libsource (lib "eagle-import") (part "R-TRIMM64W"))
    )
    (comp (ref "OFFSET_REFB")
      (value "R-TRIMM64W")
      (footprint "eagle-import:RTRIM64W")
      (libsource (lib "eagle-import") (part "R-TRIMM64W"))
    )
    (comp (ref "R2")
      (value "10k")
      (footprint "eagle-import:0603")
      (libsource (lib "eagle-import") (part "R-EU_0603"))
    )
    (comp (ref "R15")
      (value "100k")
      (footprint "eagle-import:0603")
      (libsource (lib "eagle-import") (part "R-EU_0603"))
    )
    (comp (ref "R17")
      (value "100k")
      (footprint "eagle-import:0603")
      (libsource (lib "eagle-import") (part "R-EU_0603"))
    )
    (comp (ref "R19")
      (value "100k")
      (footprint "eagle-import:0603")
      (libsource (lib "eagle-import") (part "R-EU_0603"))
    )
    (comp (ref "R23")
      (value "100k")
      (footprint "eagle-import:0603")
      (libsource (lib "eagle-import") (part "R-EU_0603"))
    )
    (comp (ref "R25")
      (value "100k")
      (footprint "eagle-import:0603")
      (libsource (lib "eagle-import") (part "R-EU_0603"))
    )
    (comp (ref "R38")
      (value "100k")
      (footprint "eagle-import:0603")
      (libsource (lib "eagle-import") (part "R-EU_0603"))
    )
    (comp (ref "R39")
      (value "100k")
      (footprint "eagle-import:0603")
      (libsource (lib "eagle-import") (part "R-EU_0603"))
    )
    (comp (ref "R40")
      (value "100k")
      (footprint "eagle-import:0603")
      (libsource (lib "eagle-import") (part "R-EU_0603"))
    )
    (comp (ref "R41")
      (value "68k")
      (footprint "eagle-import:0603")
      (libsource (lib "eagle-import") (part "R-EU_0603"))
    )
    (comp (ref "R42")
      (value "100k")
      (footprint "eagle-import:0603")
      (libsource (lib "eagle-import") (part "R-EU_0603"))
    )
    (comp (ref "R43")
      (value "100k")
      (footprint "eagle-import:0603")
      (libsource (lib "eagle-import") (part "R-EU_0603"))
    )
    (comp (ref "R46")
      (value "100k")
      (footprint "eagle-import:0603")
      (libsource (lib "eagle-import") (part "R-EU_0603"))
    )
    (comp (ref "R95")
      (value "100k")
      (footprint "eagle-import:0603")
      (libsource (lib "eagle-import") (part "R-EU_0603"))
    )
    (comp (ref "R96")
      (value "100k")
      (footprint "eagle-import:0603")
      (libsource (lib "eagle-import") (part "R-EU_0603"))
    )
    (comp (ref "R97")
      (value "100k")
      (footprint "eagle-import:0603")
      (libsource (lib "eagle-import") (part "R-EU_0603"))
    )
    (comp (ref "R98")
      (value "100k")
      (footprint "eagle-import:0603")
      (libsource (lib "eagle-import") (part "R-EU_0603"))
    )
    (comp (ref "R99")
      (value "68k")
      (footprint "eagle-import:0603")
      (libsource (lib "eagle-import") (part "R-EU_0603"))
    )
    (comp (ref "R100")
      (value "100k")
      (footprint "eagle-import:0603")
      (libsource (lib "eagle-import") (part "R-EU_0603"))
    )
    (comp (ref "R101")
      (value "100k")
      (footprint "eagle-import:0603")
      (libsource (lib "eagle-import") (part "R-EU_0603"))
    )
    (comp (ref "R102")
      (value "100k")
      (footprint "eagle-import:0603")
      (libsource (lib "eagle-import") (part "R-EU_0603"))
    )
    (comp (ref "R103")
      (value "100k")
      (footprint "eagle-import:0603")
      (libsource (lib "eagle-import") (part "R-EU_0603"))
    )
    (comp (ref "R104")
      (value "100k")
      (footprint "eagle-import:0603")
      (libsource (lib "eagle-import") (part "R-EU_0603"))
    )
    (comp (ref "R105")
      (value "100k")
      (footprint "eagle-import:0603")
      (libsource (lib "eagle-import") (part "R-EU_0603"))
    )
    (comp (ref "R106")
      (value "10k")
      (footprint "eagle-import:0603")
      (libsource (lib "eagle-import") (part "R-EU_0603"))
    )
    (comp (ref "R107")
      (value "100k")
      (footprint "eagle-import:0603")
      (libsource (lib "eagle-import") (part "R-EU_0603"))
    )
    (comp (ref "R108")
      (value "68k")
      (footprint "eagle-import:0603")
      (libsource (lib "eagle-import") (part "R-EU_0603"))
    )
    (comp (ref "R109")
      (value "100k")
      (footprint "eagle-import:0603")
      (libsource (lib "eagle-import") (part "R-EU_0603"))
    )
  )
  (nets
    (net (code "1") (name "+12V") (class "Default")
      (node (ref "C21") (pin "1") (pinfunction "1_1") (pintype "passive"))
      (node (ref "C23") (pin "1") (pinfunction "1_1") (pintype "passive"))
      (node (ref "C26") (pin "1") (pinfunction "1_1") (pintype "passive"))
      (node (ref "C28") (pin "1") (pinfunction "1_1") (pintype "passive"))
      (node (ref "C30") (pin "1") (pinfunction "1_1") (pintype "passive"))
      (node (ref "C32") (pin "1") (pinfunction "1_1") (pintype "passive"))
      (node (ref "C34") (pin "1") (pinfunction "1_1") (pintype "passive"))
      (node (ref "C36") (pin "1") (pinfunction "1_1") (pintype "passive"))
      (node (ref "C38") (pin "1") (pinfunction "1_1") (pintype "passive"))
      (node (ref "C40") (pin "1") (pinfunction "1_1") (pintype "passive"))
      (node (ref "C42") (pin "1") (pinfunction "1_1") (pintype "passive"))
      (node (ref "C44") (pin "1") (pinfunction "1_1") (pintype "passive"))
      (node (ref "C46") (pin "1") (pinfunction "1_1") (pintype "passive"))
      (node (ref "IC1") (pin "4") (pinfunction "V+_4") (pintype "power_in"))
      (node (ref "IC10") (pin "4") (pinfunction "V+_4") (pintype "power_in"))
      (node (ref "IC11") (pin "8") (pinfunction "V+_8") (pintype "power_in"))
      (node (ref "IC12") (pin "4") (pinfunction "V+_4") (pintype "power_in"))
      (node (ref "IC14") (pin "4") (pinfunction "V+_4") (pintype "power_in"))
      (node (ref "IC2") (pin "16") (pinfunction "V+_16") (pintype "power_in"))
      (node (ref "IC3") (pin "4") (pinfunction "V+_4") (pintype "power_in"))
      (node (ref "IC4") (pin "8") (pinfunction "V+_8") (pintype "power_in"))
      (node (ref "IC5") (pin "4") (pinfunction "V+_4") (pintype "power_in"))
      (node (ref "IC6") (pin "16") (pinfunction "V+_16") (pintype "power_in"))
      (node (ref "IC7") (pin "4") (pinfunction "V+_4") (pintype "power_in"))
      (node (ref "IC8") (pin "4") (pinfunction "V+_4") (pintype "power_in"))
      (node (ref "IC9") (pin "4") (pinfunction "V+_4") (pintype "power_in"))
      (node (ref "Q9") (pin "2") (pinfunction "S_2") (pintype "passive"))
      (node (ref "R106") (pin "2") (pinfunction "2_2") (pintype "passive"))
      (node (ref "R110") (pin "2") (pinfunction "2_2") (pintype "passive"))
      (node (ref "R112") (pin "2") (pinfunction "2_2") (pintype "passive"))
      (node (ref "R114") (pin "2") (pinfunction "2_2") (pintype "passive"))
      (node (ref "R117") (pin "1") (pinfunction "1_1") (pintype "passive"))
      (node (ref "R121") (pin "1") (pinfunction "1_1") (pintype "passive"))
      (node (ref "R124") (pin "2") (pinfunction "2_2") (pintype "passive"))
      (node (ref "R127") (pin "2") (pinfunction "2_2") (pintype "passive"))
      (node (ref "R13") (pin "2") (pinfunction "2_2") (pintype "passive"))
      (node (ref "R2") (pin "2") (pinfunction "2_2") (pintype "passive"))
      (node (ref "R62") (pin "2") (pinfunction "2_2") (pintype "passive"))
      (node (ref "R93") (pin "2") (pinfunction "2_2") (pintype "passive"))
      (node (ref "R94") (pin "2") (pinfunction "2_2") (pintype "passive"))
    )
    (net (code "2") (name "-12V") (class "Default")
      (node (ref "C22") (pin "2") (pinfunction "2_2") (pintype "passive"))
      (node (ref "C25") (pin "1") (pinfunction "1_1") (pintype "passive"))
      (node (ref "C27") (pin "1") (pinfunction "1_1") (pintype "passive"))
      (node (ref "C29") (pin "1") (pinfunction "1_1") (pintype "passive"))
      (node (ref "C31") (pin "1") (pinfunction "1_1") (pintype "passive"))
      (node (ref "C33") (pin "1") (pinfunction "1_1") (pintype "passive"))
      (node (ref "C35") (pin "1") (pinfunction "1_1") (pintype "passive"))
      (node (ref "C37") (pin "1") (pinfunction "1_1") (pintype "passive"))
      (node (ref "C39") (pin "1") (pinfunction "1_1") (pintype "passive"))
      (node (ref "C41") (pin "1") (pinfunction "1_1") (pintype "passive"))
      (node (ref "C43") (pin "2") (pinfunction "2_2") (pintype "passive"))
      (node (ref "C45") (pin "1") (pinfunction "1_1") (pintype "passive"))
      (node (ref "C47") (pin "1") (pinfunction "1_1") (pintype "passive"))
      (node (ref "D7") (pin "3") (pinfunction "AA_3") (pintype "passive"))
      (node (ref "D9") (pin "3") (pinfunction "AA_3") (pintype "passive"))
      (node (ref "IC1") (pin "11") (pinfunction "V-_11") (pintype "power_in"))
      (node (ref "IC10") (pin "11") (pinfunction "V-_11") (pintype "power_in"))
      (node (ref "IC11") (pin "4") (pinfunction "V-_4") (pintype "power_in"))
      (node (ref "IC12") (pin "11") (pinfunction "V-_11") (pintype "power_in"))
      (node (ref "IC14") (pin "11") (pinfunction "V-_11") (pintype "power_in"))
      (node (ref "IC2") (pin "9") (pinfunction "V-_9") (pintype "power_in"))
      (node (ref "IC3") (pin "11") (pinfunction "V-_11") (pintype "power_in"))
      (node (ref "IC4") (pin "4") (pinfunction "V-_4") (pintype "power_in"))
      (node (ref "IC5") (pin "11") (pinfunction "V-_11") (pintype "power_in"))
      (node (ref "IC6") (pin "9") (pinfunction "V-_9") (pintype "power_in"))
      (node (ref "IC7") (pin "11") (pinfunction "V-_11") (pintype "power_in"))
      (node (ref "IC8") (pin "11") (pinfunction "V-_11") (pintype "power_in"))
      (node (ref "IC9") (pin "11") (pinfunction "V-_11") (pintype "power_in"))
      (node (ref "Q10") (pin "2") (pinfunction "S_2") (pintype "passive"))
      (node (ref "R118") (pin "2") (pinfunction "2_2") (pintype "passive"))
      (node (ref "R122") (pin "2") (pinfunction "2_2") (pintype "passive"))
      (node (ref "R37") (pin "2") (pinfunction "2_2") (pintype "passive"))
      (node (ref "R61") (pin "2") (pinfunction "2_2") (pintype "passive"))
      (node (ref "R63") (pin "1") (pinfunction "1_1") (pintype "passive"))
      (node (ref "R86") (pin "2") (pinfunction "2_2") (pintype "passive"))
      (node (ref "R91") (pin "2") (pinfunction "2_2") (pintype "passive"))
    )
    (net (code "3") (name "CLAMP_REF") (class "Default")
      (node (ref "D1") (pin "3") (pinfunction "AA_3") (pintype "passive"))
      (node (ref "D2") (pin "3") (pinfunction "AA_3") (pintype "passive"))
      (node (ref "IC4") (pin "1") (pinfunction "OUT_1") (pintype "output"))
      (node (ref "IC4") (pin "2") (pinfunction "-IN_2") (pintype "input"))
    )
    (net (code "4") (name "CV_EPXB") (class "Default")
      (node (ref "JP12") (pin "2") (pinfunction "2_2") (pintype "passive"))
    )
    (net (code "5") (name "CV_EXPA") (class "Default")
      (node (ref "CV_EXP_A") (pin "P$3") (pinfunction "3_P$3") (pintype "passive"))
      (node (ref "CV_LIN_A") (pin "P$2") (pinfunction "4_P$2") (pintype "passive"))
      (node (ref "JP11") (pin "4") (pinfunction "4_4") (pintype "passive"))
      (node (ref "JP12") (pin "4") (pinfunction "4_4") (pintype "passive"))
      (node (ref "R65") (pin "1") (pinfunction "1_1") (pintype "passive"))
    )
    (net (code "6") (name "CV_EXPB") (class "Default")
      (node (ref "CV_EXP_B") (pin "P$3") (pinfunction "3_P$3") (pintype "passive"))
      (node (ref "CV_LIN_B") (pin "P$2") (pinfunction "4_P$2") (pintype "passive"))
      (node (ref "JP11") (pin "2") (pinfunction "2_2") (pintype "passive"))
      (node (ref "R74") (pin "1") (pinfunction "1_1") (pintype "passive"))
    )
    (net (code "7") (name "CV_LINA") (class "Default")
      (node (ref "CV_EXP_A") (pin "P$2") (pinfunction "4_P$2") (pintype "passive"))
      (node (ref "CV_LIN_A") (pin "P$3") (pinfunction "3_P$3") (pintype "passive"))
      (node (ref "JP11") (pin "5") (pinfunction "5_5") (pintype "passive"))
      (node (ref "JP12") (pin "5") (pinfunction "5_5") (pintype "passive"))
      (node (ref "R52") (pin "1") (pinfunction "1_1") (pintype "passive"))
    )
    (net (code "8") (name "CV_LINB") (class "Default")
      (node (ref "CV_EXP_B") (pin "P$2") (pinfunction "4_P$2") (pintype "passive"))
      (node (ref "CV_LIN_B") (pin "P$3") (pinfunction "3_P$3") (pintype "passive"))
      (node (ref "JP11") (pin "1") (pinfunction "1_1") (pintype "passive"))
      (node (ref "JP12") (pin "1") (pinfunction "1_1") (pintype "passive"))
      (node (ref "R72") (pin "1") (pinfunction "1_1") (pintype "passive"))
    )
    (net (code "9") (name "CV_SUM+_A") (class "Default")
      (node (ref "IC14") (pin "7") (pinfunction "OUT_7") (pintype "output"))
      (node (ref "R38") (pin "1") (pinfunction "1_1") (pintype "passive"))
      (node (ref "R51") (pin "2") (pinfunction "2_2") (pintype "passive"))
    )
    (net (code "10") (name "CV_SUM+_B") (class "Default")
      (node (ref "IC3") (pin "8") (pinfunction "OUT_8") (pintype "output"))
      (node (ref "R69") (pin "2") (pinfunction "2_2") (pintype "passive"))
      (node (ref "R95") (pin "2") (pinfunction "2_2") (pintype "passive"))
    )
    (net (code "11") (name "CV_SUM-_A") (class "Default")
      (node (ref "IC3") (pin "7") (pinfunction "OUT_7") (pintype "output"))
      (node (ref "R43") (pin "2") (pinfunction "2_2") (pintype "passive"))
      (node (ref "R44") (pin "2") (pinfunction "2_2") (pintype "passive"))
    )
    (net (code "12") (name "CV_SUM-_B") (class "Default")
      (node (ref "IC3") (pin "14") (pinfunction "OUT_14") (pintype "output"))
      (node (ref "R105") (pin "2") (pinfunction "2_2") (pintype "passive"))
      (node (ref "R70") (pin "2") (pinfunction "2_2") (pintype "passive"))
    )
    (net (code "13") (name "EXP_NEG_A") (class "Default")
      (node (ref "D5") (pin "2") (pinfunction "C2_2") (pintype "passive"))
      (node (ref "R40") (pin "2") (pinfunction "2_2") (pintype "passive"))
    )
    (net (code "14") (name "EXP_NEG_B") (class "Default")
      (node (ref "D6") (pin "2") (pinfunction "C2_2") (pintype "passive"))
      (node (ref "R107") (pin "2") (pinfunction "2_2") (pintype "passive"))
    )
    (net (code "15") (name "EXP_POS_A") (class "Default")
      (node (ref "D5") (pin "1") (pinfunction "A1_1") (pintype "passive"))
      (node (ref "R42") (pin "2") (pinfunction "2_2") (pintype "passive"))
    )
    (net (code "16") (name "EXP_POS_B") (class "Default")
      (node (ref "D6") (pin "1") (pinfunction "A1_1") (pintype "passive"))
      (node (ref "R101") (pin "2") (pinfunction "2_2") (pintype "passive"))
    )
    (net (code "17") (name "GND") (class "Default")
      (node (ref "140K") (pin "1") (pinfunction "1_1") (pintype "passive"))
      (node (ref "140K1") (pin "1") (pinfunction "1_1") (pintype "passive"))
      (node (ref "140K2") (pin "1") (pinfunction "1_1") (pintype "passive"))
      (node (ref "140K3") (pin "1") (pinfunction "1_1") (pintype "passive"))
      (node (ref "C1") (pin "2") (pinfunction "2_2") (pintype "passive"))
      (node (ref "C10") (pin "2") (pinfunction "2_2") (pintype "passive"))
      (node (ref "C11") (pin "2") (pinfunction "2_2") (pintype "passive"))
      (node (ref "C15") (pin "2") (pinfunction "2_2") (pintype "passive"))
      (node (ref "C17") (pin "2") (pinfunction "2_2") (pintype "passive"))
      (node (ref "C19") (pin "2") (pinfunction "2_2") (pintype "passive"))
      (node (ref "C2") (pin "2") (pinfunction "2_2") (pintype "passive"))
      (node (ref "C20") (pin "2") (pinfunction "2_2") (pintype "passive"))
      (node (ref "C21") (pin "2") (pinfunction "2_2") (pintype "passive"))
      (node (ref "C22") (pin "1") (pinfunction "1_1") (pintype "passive"))
      (node (ref "C23") (pin "2") (pinfunction "2_2") (pintype "passive"))
      (node (ref "C24") (pin "2") (pinfunction "2_2") (pintype "passive"))
      (node (ref "C25") (pin "2") (pinfunction "2_2") (pintype "passive"))
      (node (ref "C26") (pin "2") (pinfunction "2_2") (pintype "passive"))
      (node (ref "C27") (pin "2") (pinfunction "2_2") (pintype "passive"))
      (node (ref "C28") (pin "2") (pinfunction "2_2") (pintype "passive"))
      (node (ref "C29") (pin "2") (pinfunction "2_2") (pintype "passive"))
      (node (ref "C3") (pin "2") (pinfunction "2_2") (pintype "passive"))
      (node (ref "C30") (pin "2") (pinfunction "2_2") (pintype "passive"))
      (node (ref "C31") (pin "2") (pinfunction "2_2") (pintype "passive"))
      (node (ref "C32") (pin "2") (pinfunction "2_2") (pintype "passive"))
      (node (ref "C33") (pin "2") (pinfunction "2_2") (pintype "passive"))
      (node (ref "C34") (pin "2") (pinfunction "2_2") (pintype "passive"))
      (node (ref "C35") (pin "2") (pinfunction "2_2") (pintype "passive"))
      (node (ref "C36") (pin "2") (pinfunction "2_2") (pintype "passive"))
      (node (ref "C37") (pin "2") (pinfunction "2_2") (pintype "passive"))
      (node (ref "C38") (pin "2") (pinfunction "2_2") (pintype "passive"))
      (node (ref "C39") (pin "2") (pinfunction "2_2") (pintype "passive"))
      (node (ref "C40") (pin "2") (pinfunction "2_2") (pintype "passive"))
      (node (ref "C41") (pin "2") (pinfunction "2_2") (pintype "passive"))
      (node (ref "C42") (pin "2") (pinfunction "2_2") (pintype "passive"))
      (node (ref "C43") (pin "1") (pinfunction "1_1") (pintype "passive"))
      (node (ref "C44") (pin "2") (pinfunction "2_2") (pintype "passive"))
      (node (ref "C45") (pin "2") (pinfunction "2_2") (pintype "passive"))
      (node (ref "C46") (pin "2") (pinfunction "2_2") (pintype "passive"))
      (node (ref "C47") (pin "2") (pinfunction "2_2") (pintype "passive"))
      (node (ref "C5") (pin "2") (pinfunction "2_2") (pintype "passive"))
      (node (ref "C7") (pin "2") (pinfunction "2_2") (pintype "passive"))
      (node (ref "C9") (pin "2") (pinfunction "2_2") (pintype "passive"))
      (node (ref "CV_EXP_A") (pin "P$1") (pinfunction "5_P$1") (pintype "passive"))
      (node (ref "CV_EXP_B") (pin "P$1") (pinfunction "5_P$1") (pintype "passive"))
      (node (ref "CV_LIN_A") (pin "P$1") (pinfunction "5_P$1") (pintype "passive"))
      (node (ref "CV_LIN_B") (pin "P$1") (pinfunction "5_P$1") (pintype "passive"))
      (node (ref "D7") (pin "1") (pinfunction "K1_1") (pintype "passive"))
      (node (ref "D7") (pin "2") (pinfunction "K2_2") (pintype "passive"))
      (node (ref "D9") (pin "1") (pinfunction "K1_1") (pintype "passive"))
      (node (ref "D9") (pin "2") (pinfunction "K2_2") (pintype "passive"))
      (node (ref "IC10") (pin "5") (pinfunction "+IN_5") (pintype "input"))
      (node (ref "IC12") (pin "3") (pinfunction "+IN_3") (pintype "input"))
      (node (ref "IC14") (pin "3") (pinfunction "+IN_3") (pintype "input"))
      (node (ref "IC2") (pin "8") (pinfunction "GND_8") (pintype "power_in"))
      (node (ref "IC4") (pin "5") (pinfunction "+IN_5") (pintype "input"))
      (node (ref "IC5") (pin "10") (pinfunction "+IN_10") (pintype "input"))
      (node (ref "IC5") (pin "5") (pinfunction "+IN_5") (pintype "input"))
      (node (ref "IC6") (pin "8") (pinfunction "GND_8") (pintype "power_in"))
      (node (ref "IC7") (pin "5") (pinfunction "+IN_5") (pintype "input"))
      (node (ref "IC8") (pin "10") (pinfunction "+IN_10") (pintype "input"))
      (node (ref "IC8") (pin "5") (pinfunction "+IN_5") (pintype "input"))
      (node (ref "IN_A") (pin "P$1") (pinfunction "5_P$1") (pintype "passive"))
      (node (ref "IN_A") (pin "P$2") (pinfunction "4_P$2") (pintype "passive"))
      (node (ref "IN_B") (pin "P$1") (pinfunction "5_P$1") (pintype "passive"))
      (node (ref "IN_B") (pin "P$2") (pinfunction "4_P$2") (pintype "passive"))
      (node (ref "J2") (pin "4") (pinfunction "4_4") (pintype "passive"))
      (node (ref "JP1") (pin "2") (pinfunction "2_2") (pintype "passive"))
      (node (ref "JP10") (pin "2") (pinfunction "2_2") (pintype "passive"))
      (node (ref "JP11") (pin "3") (pinfunction "3_3") (pintype "passive"))
      (node (ref "JP12") (pin "3") (pinfunction "3_3") (pintype "passive"))
      (node (ref "JP13") (pin "2") (pinfunction "2_2") (pintype "passive"))
      (node (ref "JP14") (pin "2") (pinfunction "2_2") (pintype "passive"))
      (node (ref "JP2") (pin "5") (pinfunction "5_5") (pintype "passive"))
      (node (ref "JP3") (pin "5") (pinfunction "5_5") (pintype "passive"))
      (node (ref "JP4") (pin "4") (pinfunction "4_4") (pintype "passive"))
      (node (ref "JP5") (pin "4") (pinfunction "4_4") (pintype "passive"))
      (node (ref "JP6") (pin "2") (pinfunction "2_2") (pintype "passive"))
      (node (ref "JP7") (pin "4") (pinfunction "4_4") (pintype "passive"))
      (node (ref "JP8") (pin "3") (pinfunction "3_3") (pintype "passive"))
      (node (ref "JP8") (pin "4") (pinfunction "4_4") (pintype "passive"))
      (node (ref "JP8") (pin "5") (pinfunction "5_5") (pintype "passive"))
      (node (ref "JP8") (pin "6") (pinfunction "6_6") (pintype "passive"))
      (node (ref "JP8") (pin "7") (pinfunction "7_7") (pintype "passive"))
      (node (ref "JP8") (pin "8") (pinfunction "8_8") (pintype "passive"))
      (node (ref "JP9") (pin "2") (pinfunction "2_2") (pintype "passive"))
      (node (ref "LD1") (pin "C") (pinfunction "C_C") (pintype "passive"))
      (node (ref "LD2") (pin "C") (pinfunction "C_C") (pintype "passive"))
      (node (ref "OFFSET_LINA") (pin "1") (pinfunction "A_1") (pintype "passive"))
      (node (ref "OFFSET_LINB") (pin "1") (pinfunction "A_1") (pintype "passive"))
      (node (ref "OFFSET_REF") (pin "1") (pinfunction "A_1") (pintype "passive"))
      (node (ref "OFFSET_REFB") (pin "1") (pinfunction "A_1") (pintype "passive"))
      (node (ref "OUT_A") (pin "P$1") (pinfunction "5_P$1") (pintype "passive"))
      (node (ref "OUT_A") (pin "P$2") (pinfunction "4_P$2") (pintype "passive"))
      (node (ref "OUT_B") (pin "P$1") (pinfunction "5_P$1") (pintype "passive"))
      (node (ref "OUT_B") (pin "P$2") (pinfunction "4_P$2") (pintype "passive"))
      (node (ref "POT_EXPA") (pin "2") (pinfunction "2_2") (pintype "bidirectional"))
      (node (ref "POT_EXPB") (pin "2") (pinfunction "2_2") (pintype "bidirectional"))
      (node (ref "POT_LINA") (pin "2") (pinfunction "2_2") (pintype "bidirectional"))
      (node (ref "POT_LINB") (pin "2") (pinfunction "2_2") (pintype "bidirectional"))
      (node (ref "Q1") (pin "C") (pinfunction "C_C") (pintype "passive"))
      (node (ref "Q10") (pin "1") (pinfunction "G_1") (pintype "passive"))
      (node (ref "Q2") (pin "C") (pinfunction "C_C") (pintype "passive"))
      (node (ref "Q3") (pin "C") (pinfunction "C_C") (pintype "passive"))
      (node (ref "Q5") (pin "C") (pinfunction "C_C") (pintype "passive"))
      (node (ref "Q9") (pin "1") (pinfunction "G_1") (pintype "passive"))
      (node (ref "R1") (pin "2") (pinfunction "2_2") (pintype "passive"))
      (node (ref "R109") (pin "1") (pinfunction "1_1") (pintype "passive"))
      (node (ref "R111") (pin "1") (pinfunction "1_1") (pintype "passive"))
      (node (ref "R113") (pin "1") (pinfunction "1_1") (pintype "passive"))
      (node (ref "R119") (pin "2") (pinfunction "2_2") (pintype "passive"))
      (node (ref "R120") (pin "2") (pinfunction "2_2") (pintype "passive"))
      (node (ref "R123") (pin "1") (pinfunction "1_1") (pintype "passive"))
      (node (ref "R126") (pin "1") (pinfunction "1_1") (pintype "passive"))
      (node (ref "R30") (pin "2") (pinfunction "2_2") (pintype "passive"))
      (node (ref "R46") (pin "1") (pinfunction "1_1") (pintype "passive"))
      (node (ref "R50") (pin "2") (pinfunction "2_2") (pintype "passive"))
      (node (ref "R71") (pin "2") (pinfunction "2_2") (pintype "passive"))
      (node (ref "R96") (pin "1") (pinfunction "1_1") (pintype "passive"))
    )
    (net (code "18") (name "IC2_4") (class "Default")
      (node (ref "C13") (pin "2") (pinfunction "2_2") (pintype "passive"))
      (node (ref "IC2") (pin "4") (pinfunction "OUT_4") (pintype "output"))
      (node (ref "IC7") (pin "9") (pinfunction "-IN_9") (pintype "input"))
      (node (ref "R33") (pin "1") (pinfunction "1_1") (pintype "passive"))
    )
    (net (code "19") (name "IC6_4") (class "Default")
      (node (ref "C18") (pin "2") (pinfunction "2_2") (pintype "passive"))
      (node (ref "IC10") (pin "13") (pinfunction "-IN_13") (pintype "input"))
      (node (ref "IC6") (pin "4") (pinfunction "OUT_4") (pintype "output"))
      (node (ref "R88") (pin "1") (pinfunction "1_1") (pintype "passive"))
    )
    (net (code "20") (name "IC6_13") (class "Default")
      (node (ref "C8") (pin "2") (pinfunction "2_2") (pintype "passive"))
      (node (ref "IC10") (pin "9") (pinfunction "-IN_9") (pintype "input"))
      (node (ref "IC6") (pin "13") (pinfunction "OUT_13") (pintype "output"))
      (node (ref "R83") (pin "1") (pinfunction "1_1") (pintype "passive"))
    )
    (net (code "21") (name "IN1") (class "Default")
      (node (ref "IC8") (pin "1") (pinfunction "OUT_1") (pintype "output"))
      (node (ref "IC8") (pin "2") (pinfunction "-IN_2") (pintype "input"))
      (node (ref "R48") (pin "1") (pinfunction "1_1") (pintype "passive"))
      (node (ref "R57") (pin "1") (pinfunction "1_1") (pintype "passive"))
    )
    (net (code "22") (name "IN2") (class "Default")
      (node (ref "IC5") (pin "1") (pinfunction "OUT_1") (pintype "output"))
      (node (ref "IC5") (pin "2") (pinfunction "-IN_2") (pintype "input"))
      (node (ref "R24") (pin "1") (pinfunction "1_1") (pintype "passive"))
      (node (ref "R9") (pin "1") (pinfunction "1_1") (pintype "passive"))
    )
    (net (code "23") (name "INV_A") (class "Default")
      (node (ref "IC5") (pin "12") (pinfunction "+IN_12") (pintype "input"))
      (node (ref "JP1") (pin "1") (pinfunction "1_1") (pintype "passive"))
      (node (ref "JP6") (pin "1") (pinfunction "1_1") (pintype "passive"))
      (node (ref "R125") (pin "1") (pinfunction "1_1") (pintype "passive"))
      (node (ref "R20") (pin "2") (pinfunction "2_2") (pintype "passive"))
      (node (ref "R30") (pin "1") (pinfunction "1_1") (pintype "passive"))
      (node (ref "S1") (pin "2") (pinfunction "P_2") (pintype "passive"))
    )
    (net (code "24") (name "INV_B") (class "Default")
      (node (ref "IC8") (pin "12") (pinfunction "+IN_12") (pintype "input"))
      (node (ref "JP1") (pin "3") (pinfunction "3_3") (pintype "passive"))
      (node (ref "JP6") (pin "3") (pinfunction "3_3") (pintype "passive"))
      (node (ref "R128") (pin "1") (pinfunction "1_1") (pintype "passive"))
      (node (ref "R66") (pin "2") (pinfunction "2_2") (pintype "passive"))
      (node (ref "R71") (pin "1") (pinfunction "1_1") (pintype "passive"))
      (node (ref "S2") (pin "2") (pinfunction "P_2") (pintype "passive"))
    )
    (net (code "25") (name "IN_A") (class "Default")
      (node (ref "IC5") (pin "3") (pinfunction "+IN_3") (pintype "input"))
      (node (ref "IN_A") (pin "P$3") (pinfunction "3_P$3") (pintype "passive"))
      (node (ref "JP13") (pin "3") (pinfunction "3_3") (pintype "passive"))
      (node (ref "JP14") (pin "3") (pinfunction "3_3") (pintype "passive"))
      (node (ref "R1") (pin "1") (pinfunction "1_1") (pintype "passive"))
    )
    (net (code "26") (name "IN_B") (class "Default")
      (node (ref "IC8") (pin "3") (pinfunction "+IN_3") (pintype "input"))
      (node (ref "IN_B") (pin "P$3") (pinfunction "3_P$3") (pintype "passive"))
      (node (ref "JP13") (pin "1") (pinfunction "1_1") (pintype "passive"))
      (node (ref "JP14") (pin "1") (pinfunction "1_1") (pintype "passive"))
      (node (ref "R50") (pin "1") (pinfunction "1_1") (pintype "passive"))
    )
    (net (code "27") (name "LED_A+") (class "Default")
      (node (ref "J2") (pin "3") (pinfunction "3_3") (pintype "passive"))
      (node (ref "LD1") (pin "AR") (pinfunction "AR_AR") (pintype "passive"))
      (node (ref "Q1") (pin "E") (pinfunction "E_E") (pintype "passive"))
      (node (ref "R114") (pin "1") (pinfunction "1_1") (pintype "passive"))
    )
    (net (code "28") (name "LED_A-") (class "Default")
      (node (ref "J2") (pin "2") (pinfunction "2_2") (pintype "passive"))
      (node (ref "LD1") (pin "AX") (pinfunction "AY_AX") (pintype "passive"))
      (node (ref "Q2") (pin "E") (pinfunction "E_E") (pintype "passive"))
      (node (ref "R124") (pin "1") (pinfunction "1_1") (pintype "passive"))
    )
    (net (code "29") (name "LED_B+") (class "Default")
      (node (ref "J2") (pin "7") (pinfunction "7_7") (pintype "passive"))
      (node (ref "JP7") (pin "1") (pinfunction "1_1") (pintype "passive"))
      (node (ref "LD2") (pin "AR") (pinfunction "AR_AR") (pintype "passive"))
      (node (ref "Q5") (pin "E") (pinfunction "E_E") (pintype "passive"))
      (node (ref "R112") (pin "1") (pinfunction "1_1") (pintype "passive"))
    )
    (net (code "30") (name "LED_B-") (class "Default")
      (node (ref "J2") (pin "6") (pinfunction "6_6") (pintype "passive"))
      (node (ref "JP7") (pin "2") (pinfunction "2_2") (pintype "passive"))
      (node (ref "LD2") (pin "AX") (pinfunction "AY_AX") (pintype "passive"))
      (node (ref "Q3") (pin "E") (pinfunction "E_E") (pintype "passive"))
      (node (ref "R127") (pin "1") (pinfunction "1_1") (pintype "passive"))
    )
    (net (code "31") (name "LIN+_OUT_A") (class "Default")
      (node (ref "C6") (pin "1") (pinfunction "1_1") (pintype "passive"))
      (node (ref "IC2") (pin "14") (pinfunction "CTRL_14") (pintype "input"))
      (node (ref "IC7") (pin "14") (pinfunction "OUT_14") (pintype "output"))
      (node (ref "R17") (pin "2") (pinfunction "2_2") (pintype "passive"))
    )
    (net (code "32") (name "LIN+_OUT_B") (class "Default")
      (node (ref "C18") (pin "1") (pinfunction "1_1") (pintype "passive"))
      (node (ref "IC10") (pin "14") (pinfunction "OUT_14") (pintype "output"))
      (node (ref "IC6") (pin "3") (pinfunction "CTRL_3") (pintype "input"))
      (node (ref "R98") (pin "1") (pinfunction "1_1") (pintype "passive"))
    )
    (net (code "33") (name "LIN-_OUT_A") (class "Default")
      (node (ref "C13") (pin "1") (pinfunction "1_1") (pintype "passive"))
      (node (ref "IC2") (pin "3") (pinfunction "CTRL_3") (pintype "input"))
      (node (ref "IC7") (pin "8") (pinfunction "OUT_8") (pintype "output"))
      (node (ref "R23") (pin "1") (pinfunction "1_1") (pintype "passive"))
    )
    (net (code "34") (name "LIN-_OUT_B") (class "Default")
      (node (ref "C8") (pin "1") (pinfunction "1_1") (pintype "passive"))
      (node (ref "IC10") (pin "8") (pinfunction "OUT_8") (pintype "output"))
      (node (ref "IC6") (pin "14") (pinfunction "CTRL_14") (pintype "input"))
      (node (ref "R104") (pin "1") (pinfunction "1_1") (pintype "passive"))
    )
    (net (code "35") (name "LINBIASA_1") (class "Default")
      (node (ref "JP4") (pin "3") (pinfunction "3_3") (pintype "passive"))
      (node (ref "JP5") (pin "3") (pinfunction "3_3") (pintype "passive"))
      (node (ref "POT_LINBIASA") (pin "1") (pinfunction "1_1") (pintype "bidirectional"))
      (node (ref "R121") (pin "2") (pinfunction "2_2") (pintype "passive"))
    )
    (net (code "36") (name "LINBIASA_2") (class "Default")
      (node (ref "JP4") (pin "2") (pinfunction "2_2") (pintype "passive"))
      (node (ref "JP5") (pin "2") (pinfunction "2_2") (pintype "passive"))
      (node (ref "POT_LINBIASA") (pin "2") (pinfunction "2_2") (pintype "bidirectional"))
      (node (ref "R53") (pin "1") (pinfunction "1_1") (pintype "passive"))
    )
    (net (code "37") (name "LINBIASA_3") (class "Default")
      (node (ref "JP4") (pin "1") (pinfunction "1_1") (pintype "passive"))
      (node (ref "JP5") (pin "1") (pinfunction "1_1") (pintype "passive"))
      (node (ref "POT_LINBIASA") (pin "3") (pinfunction "3_3") (pintype "bidirectional"))
      (node (ref "R122") (pin "1") (pinfunction "1_1") (pintype "passive"))
    )
    (net (code "38") (name "LINBIASB_1") (class "Default")
      (node (ref "JP4") (pin "7") (pinfunction "7_7") (pintype "passive"))
      (node (ref "JP5") (pin "7") (pinfunction "7_7") (pintype "passive"))
      (node (ref "POT_LINBIASB") (pin "1") (pinfunction "1_1") (pintype "bidirectional"))
      (node (ref "R117") (pin "2") (pinfunction "2_2") (pintype "passive"))
    )
    (net (code "39") (name "LINBIASB_2") (class "Default")
      (node (ref "JP4") (pin "6") (pinfunction "6_6") (pintype "passive"))
      (node (ref "JP5") (pin "6") (pinfunction "6_6") (pintype "passive"))
      (node (ref "POT_LINBIASB") (pin "2") (pinfunction "2_2") (pintype "bidirectional"))
      (node (ref "R73") (pin "1") (pinfunction "1_1") (pintype "passive"))
    )
    (net (code "40") (name "LINBIASB_3") (class "Default")
      (node (ref "JP4") (pin "5") (pinfunction "5_5") (pintype "passive"))
      (node (ref "JP5") (pin "5") (pinfunction "5_5") (pintype "passive"))
      (node (ref "POT_LINBIASB") (pin "3") (pinfunction "3_3") (pintype "bidirectional"))
      (node (ref "R118") (pin "1") (pinfunction "1_1") (pintype "passive"))
    )
    (net (code "41") (name "LIN_NEG_A") (class "Default")
      (node (ref "D3") (pin "2") (pinfunction "C2_2") (pintype "passive"))
      (node (ref "R32") (pin "1") (pinfunction "1_1") (pintype "passive"))
    )
    (net (code "42") (name "LIN_NEG_B") (class "Default")
      (node (ref "D4") (pin "2") (pinfunction "C2_2") (pintype "passive"))
      (node (ref "R16") (pin "1") (pinfunction "1_1") (pintype "passive"))
    )
    (net (code "43") (name "LIN_POS_A") (class "Default")
      (node (ref "D3") (pin "1") (pinfunction "A1_1") (pintype "passive"))
      (node (ref "R55") (pin "1") (pinfunction "1_1") (pintype "passive"))
    )
    (net (code "44") (name "LIN_POS_B") (class "Default")
      (node (ref "D4") (pin "1") (pinfunction "A1_1") (pintype "passive"))
      (node (ref "R87") (pin "1") (pinfunction "1_1") (pintype "passive"))
    )
    (net (code "45") (name "Net-(140K-Pad2)") (class "Default")
      (node (ref "140K") (pin "2") (pinfunction "2_2") (pintype "passive"))
      (node (ref "R34") (pin "1") (pinfunction "1_1") (pintype "passive"))
      (node (ref "R37") (pin "1") (pinfunction "1_1") (pintype "passive"))
    )
    (net (code "46") (name "Net-(140K1-Pad2)") (class "Default")
      (node (ref "140K1") (pin "2") (pinfunction "2_2") (pintype "passive"))
      (node (ref "R59") (pin "1") (pinfunction "1_1") (pintype "passive"))
      (node (ref "R61") (pin "1") (pinfunction "1_1") (pintype "passive"))
    )
    (net (code "47") (name "Net-(140K2-Pad2)") (class "Default")
      (node (ref "140K2") (pin "2") (pinfunction "2_2") (pintype "passive"))
      (node (ref "R84") (pin "1") (pinfunction "1_1") (pintype "passive"))
      (node (ref "R86") (pin "1") (pinfunction "1_1") (pintype "passive"))
    )
    (net (code "48") (name "Net-(140K3-Pad2)") (class "Default")
      (node (ref "140K3") (pin "2") (pinfunction "2_2") (pintype "passive"))
      (node (ref "R89") (pin "1") (pinfunction "1_1") (pintype "passive"))
      (node (ref "R91") (pin "1") (pinfunction "1_1") (pintype "passive"))
    )
    (net (code "49") (name "Net-(C2-Pad1)") (class "Default")
      (node (ref "C2") (pin "1") (pinfunction "1_1") (pintype "passive"))
      (node (ref "R35") (pin "1") (pinfunction "1_1") (pintype "passive"))
    )
    (net (code "50") (name "Net-(C3-Pad1)") (class "Default")
      (node (ref "C3") (pin "1") (pinfunction "1_1") (pintype "passive"))
      (node (ref "R6") (pin "1") (pinfunction "1_1") (pintype "passive"))
    )
    (net (code "51") (name "Net-(C5-Pad1)") (class "Default")
      (node (ref "C5") (pin "1") (pinfunction "1_1") (pintype "passive"))
      (node (ref "R11") (pin "1") (pinfunction "1_1") (pintype "passive"))
    )
    (net (code "52") (name "Net-(C7-Pad1)") (class "Default")
      (node (ref "C7") (pin "1") (pinfunction "1_1") (pintype "passive"))
      (node (ref "R60") (pin "1") (pinfunction "1_1") (pintype "passive"))
    )
    (net (code "53") (name "Net-(C11-Pad1)") (class "Default")
      (node (ref "C11") (pin "1") (pinfunction "1_1") (pintype "passive"))
      (node (ref "R47") (pin "1") (pinfunction "1_1") (pintype "passive"))
    )
    (net (code "54") (name "Net-(C15-Pad1)") (class "Default")
      (node (ref "C15") (pin "1") (pinfunction "1_1") (pintype "passive"))
      (node (ref "R56") (pin "1") (pinfunction "1_1") (pintype "passive"))
    )
    (net (code "55") (name "Net-(C17-Pad1)") (class "Default")
      (node (ref "C17") (pin "1") (pinfunction "1_1") (pintype "passive"))
      (node (ref "R85") (pin "1") (pinfunction "1_1") (pintype "passive"))
    )
    (net (code "56") (name "Net-(C19-Pad1)") (class "Default")
      (node (ref "C19") (pin "1") (pinfunction "1_1") (pintype "passive"))
      (node (ref "R90") (pin "1") (pinfunction "1_1") (pintype "passive"))
    )
    (net (code "57") (name "Net-(CLAMP_REF-A)") (class "Default")
      (node (ref "CLAMP_REF") (pin "1") (pinfunction "A_1") (pintype "passive"))
      (node (ref "R63") (pin "2") (pinfunction "2_2") (pintype "passive"))
    )
    (net (code "58") (name "Net-(CLAMP_REF-E)") (class "Default")
      (node (ref "CLAMP_REF") (pin "3") (pinfunction "E_3") (pintype "passive"))
      (node (ref "R62") (pin "1") (pinfunction "1_1") (pintype "passive"))
    )
    (net (code "59") (name "Net-(CLAMP_REF-S)") (class "Default")
      (node (ref "C10") (pin "1") (pinfunction "1_1") (pintype "passive"))
      (node (ref "CLAMP_REF") (pin "2") (pinfunction "S_2") (pintype "passive"))
      (node (ref "IC4") (pin "3") (pinfunction "+IN_3") (pintype "input"))
    )
    (net (code "60") (name "Net-(D1-K1)") (class "Default")
      (node (ref "D1") (pin "1") (pinfunction "K1_1") (pintype "passive"))
      (node (ref "IC2") (pin "6") (pinfunction "CTRL_6") (pintype "input"))
      (node (ref "R44") (pin "1") (pinfunction "1_1") (pintype "passive"))
    )
    (net (code "61") (name "Net-(D1-K2)") (class "Default")
      (node (ref "D1") (pin "2") (pinfunction "K2_2") (pintype "passive"))
      (node (ref "IC2") (pin "11") (pinfunction "CTRL_11") (pintype "input"))
      (node (ref "R51") (pin "1") (pinfunction "1_1") (pintype "passive"))
    )
    (net (code "62") (name "Net-(D2-K1)") (class "Default")
      (node (ref "D2") (pin "1") (pinfunction "K1_1") (pintype "passive"))
      (node (ref "IC6") (pin "6") (pinfunction "CTRL_6") (pintype "input"))
      (node (ref "R70") (pin "1") (pinfunction "1_1") (pintype "passive"))
    )
    (net (code "63") (name "Net-(D2-K2)") (class "Default")
      (node (ref "D2") (pin "2") (pinfunction "K2_2") (pintype "passive"))
      (node (ref "IC6") (pin "11") (pinfunction "CTRL_11") (pintype "input"))
      (node (ref "R69") (pin "1") (pinfunction "1_1") (pintype "passive"))
    )
    (net (code "64") (name "Net-(D3-C1A2)") (class "Default")
      (node (ref "D3") (pin "3") (pinfunction "C1A2_3") (pintype "passive"))
      (node (ref "IC1") (pin "8") (pinfunction "OUT_8") (pintype "output"))
      (node (ref "R4") (pin "2") (pinfunction "2_2") (pintype "passive"))
    )
    (net (code "65") (name "Net-(D4-C1A2)") (class "Default")
      (node (ref "D4") (pin "3") (pinfunction "C1A2_3") (pintype "passive"))
      (node (ref "IC9") (pin "8") (pinfunction "OUT_8") (pintype "output"))
      (node (ref "R79") (pin "2") (pinfunction "2_2") (pintype "passive"))
    )
    (net (code "66") (name "Net-(D5-C1A2)") (class "Default")
      (node (ref "D5") (pin "3") (pinfunction "C1A2_3") (pintype "passive"))
      (node (ref "IC1") (pin "14") (pinfunction "OUT_14") (pintype "output"))
      (node (ref "R21") (pin "2") (pinfunction "2_2") (pintype "passive"))
    )
    (net (code "67") (name "Net-(D6-C1A2)") (class "Default")
      (node (ref "D6") (pin "3") (pinfunction "C1A2_3") (pintype "passive"))
      (node (ref "IC9") (pin "14") (pinfunction "OUT_14") (pintype "output"))
      (node (ref "R76") (pin "2") (pinfunction "2_2") (pintype "passive"))
    )
    (net (code "68") (name "Net-(IC1A-+IN)") (class "Default")
      (node (ref "IC1") (pin "3") (pinfunction "+IN_3") (pintype "input"))
      (node (ref "R52") (pin "2") (pinfunction "2_2") (pintype "passive"))
    )
    (net (code "69") (name "Net-(IC1A--IN)") (class "Default")
      (node (ref "IC1") (pin "1") (pinfunction "OUT_1") (pintype "output"))
      (node (ref "IC1") (pin "2") (pinfunction "-IN_2") (pintype "input"))
      (node (ref "R12") (pin "1") (pinfunction "1_1") (pintype "passive"))
      (node (ref "R3") (pin "1") (pinfunction "1_1") (pintype "passive"))
    )
    (net (code "70") (name "Net-(IC1B-+IN)") (class "Default")
      (node (ref "IC1") (pin "5") (pinfunction "+IN_5") (pintype "input"))
      (node (ref "R65") (pin "2") (pinfunction "2_2") (pintype "passive"))
    )
    (net (code "71") (name "Net-(IC1B--IN)") (class "Default")
      (node (ref "IC1") (pin "6") (pinfunction "-IN_6") (pintype "input"))
      (node (ref "IC1") (pin "7") (pinfunction "OUT_7") (pintype "output"))
      (node (ref "R22") (pin "1") (pinfunction "1_1") (pintype "passive"))
      (node (ref "R31") (pin "1") (pinfunction "1_1") (pintype "passive"))
    )
    (net (code "72") (name "Net-(IC1C--IN)") (class "Default")
      (node (ref "IC1") (pin "9") (pinfunction "-IN_9") (pintype "input"))
      (node (ref "R3") (pin "2") (pinfunction "2_2") (pintype "passive"))
      (node (ref "R4") (pin "1") (pinfunction "1_1") (pintype "passive"))
      (node (ref "R53") (pin "2") (pinfunction "2_2") (pintype "passive"))
      (node (ref "R8") (pin "1") (pinfunction "1_1") (pintype "passive"))
    )
    (net (code "73") (name "Net-(IC1D--IN)") (class "Default")
      (node (ref "IC1") (pin "13") (pinfunction "-IN_13") (pintype "input"))
      (node (ref "R14") (pin "1") (pinfunction "1_1") (pintype "passive"))
      (node (ref "R21") (pin "1") (pinfunction "1_1") (pintype "passive"))
      (node (ref "R31") (pin "2") (pinfunction "2_2") (pintype "passive"))
    )
    (net (code "74") (name "Net-(IC2A-IN)") (class "Default")
      (node (ref "IC2") (pin "2") (pinfunction "IN_2") (pintype "input"))
      (node (ref "R34") (pin "2") (pinfunction "2_2") (pintype "passive"))
      (node (ref "R35") (pin "2") (pinfunction "2_2") (pintype "passive"))
    )
    (net (code "75") (name "Net-(IC2B-IN)") (class "Default")
      (node (ref "IC2") (pin "7") (pinfunction "IN_7") (pintype "input"))
      (node (ref "R5") (pin "2") (pinfunction "2_2") (pintype "passive"))
      (node (ref "R6") (pin "2") (pinfunction "2_2") (pintype "passive"))
    )
    (net (code "76") (name "Net-(IC2B-OUT)") (class "Default")
      (node (ref "C4") (pin "2") (pinfunction "2_2") (pintype "passive"))
      (node (ref "IC2") (pin "5") (pinfunction "OUT_5") (pintype "output"))
      (node (ref "IC5") (pin "6") (pinfunction "-IN_6") (pintype "input"))
      (node (ref "R10") (pin "1") (pinfunction "1_1") (pintype "passive"))
    )
    (net (code "77") (name "Net-(IC2C-IN)") (class "Default")
      (node (ref "IC2") (pin "10") (pinfunction "IN_10") (pintype "input"))
      (node (ref "R11") (pin "2") (pinfunction "2_2") (pintype "passive"))
      (node (ref "R7") (pin "2") (pinfunction "2_2") (pintype "passive"))
    )
    (net (code "78") (name "Net-(IC2C-OUT)") (class "Default")
      (node (ref "C12") (pin "2") (pinfunction "2_2") (pintype "passive"))
      (node (ref "IC2") (pin "12") (pinfunction "OUT_12") (pintype "output"))
      (node (ref "IC5") (pin "9") (pinfunction "-IN_9") (pintype "input"))
      (node (ref "R36") (pin "1") (pinfunction "1_1") (pintype "passive"))
    )
    (net (code "79") (name "Net-(IC2D-IN)") (class "Default")
      (node (ref "IC2") (pin "15") (pinfunction "IN_15") (pintype "input"))
      (node (ref "R59") (pin "2") (pinfunction "2_2") (pintype "passive"))
      (node (ref "R60") (pin "2") (pinfunction "2_2") (pintype "passive"))
    )
    (net (code "80") (name "Net-(IC2D-OUT)") (class "Default")
      (node (ref "C6") (pin "2") (pinfunction "2_2") (pintype "passive"))
      (node (ref "IC2") (pin "13") (pinfunction "OUT_13") (pintype "output"))
      (node (ref "IC7") (pin "13") (pinfunction "-IN_13") (pintype "input"))
      (node (ref "R58") (pin "1") (pinfunction "1_1") (pintype "passive"))
    )
    (net (code "81") (name "Net-(IC2E-MODE)") (class "Default")
      (node (ref "IC2") (pin "1") (pinfunction "MODE_1") (pintype "input"))
      (node (ref "R94") (pin "1") (pinfunction "1_1") (pintype "passive"))
    )
    (net (code "82") (name "Net-(IC3B-+IN)") (class "Default")
      (node (ref "IC3") (pin "5") (pinfunction "+IN_5") (pintype "input"))
      (node (ref "R19") (pin "2") (pinfunction "2_2") (pintype "passive"))
      (node (ref "R23") (pin "2") (pinfunction "2_2") (pintype "passive"))
    )
    (net (code "83") (name "Net-(IC3B--IN)") (class "Default")
      (node (ref "IC3") (pin "6") (pinfunction "-IN_6") (pintype "input"))
      (node (ref "R43") (pin "1") (pinfunction "1_1") (pintype "passive"))
      (node (ref "R46") (pin "2") (pinfunction "2_2") (pintype "passive"))
    )
    (net (code "84") (name "Net-(IC3C-+IN)") (class "Default")
      (node (ref "IC3") (pin "10") (pinfunction "+IN_10") (pintype "input"))
      (node (ref "R97") (pin "2") (pinfunction "2_2") (pintype "passive"))
      (node (ref "R98") (pin "2") (pinfunction "2_2") (pintype "passive"))
    )
    (net (code "85") (name "Net-(IC3C--IN)") (class "Default")
      (node (ref "IC3") (pin "9") (pinfunction "-IN_9") (pintype "input"))
      (node (ref "R95") (pin "1") (pinfunction "1_1") (pintype "passive"))
      (node (ref "R96") (pin "2") (pinfunction "2_2") (pintype "passive"))
    )
    (net (code "86") (name "Net-(IC3D-+IN)") (class "Default")
      (node (ref "IC3") (pin "12") (pinfunction "+IN_12") (pintype "input"))
      (node (ref "R103") (pin "2") (pinfunction "2_2") (pintype "passive"))
      (node (ref "R104") (pin "2") (pinfunction "2_2") (pintype "passive"))
    )
    (net (code "87") (name "Net-(IC3D--IN)") (class "Default")
      (node (ref "IC3") (pin "13") (pinfunction "-IN_13") (pintype "input"))
      (node (ref "R105") (pin "1") (pinfunction "1_1") (pintype "passive"))
      (node (ref "R109") (pin "2") (pinfunction "2_2") (pintype "passive"))
    )
    (net (code "88") (name "Net-(IC4B--IN)") (class "Default")
      (node (ref "IC4") (pin "6") (pinfunction "-IN_6") (pintype "input"))
      (node (ref "IC4") (pin "7") (pinfunction "OUT_7") (pintype "output"))
    )
    (net (code "89") (name "Net-(IC5B-OUT)") (class "Default")
      (node (ref "C4") (pin "1") (pinfunction "1_1") (pintype "passive"))
      (node (ref "IC5") (pin "7") (pinfunction "OUT_7") (pintype "output"))
      (node (ref "R10") (pin "2") (pinfunction "2_2") (pintype "passive"))
      (node (ref "R20") (pin "1") (pinfunction "1_1") (pintype "passive"))
    )
    (net (code "90") (name "Net-(IC5C-OUT)") (class "Default")
      (node (ref "C12") (pin "1") (pinfunction "1_1") (pintype "passive"))
      (node (ref "IC5") (pin "8") (pinfunction "OUT_8") (pintype "output"))
      (node (ref "R29") (pin "1") (pinfunction "1_1") (pintype "passive"))
      (node (ref "R36") (pin "2") (pinfunction "2_2") (pintype "passive"))
    )
    (net (code "91") (name "Net-(IC5D--IN)") (class "Default")
      (node (ref "IC5") (pin "13") (pinfunction "-IN_13") (pintype "input"))
      (node (ref "R115") (pin "1") (pinfunction "1_1") (pintype "passive"))
      (node (ref "R28") (pin "1") (pinfunction "1_1") (pintype "passive"))
      (node (ref "R29") (pin "2") (pinfunction "2_2") (pintype "passive"))
    )
    (net (code "92") (name "Net-(IC5D-OUT)") (class "Default")
      (node (ref "1K") (pin "1") (pinfunction "1_1") (pintype "passive"))
      (node (ref "IC5") (pin "14") (pinfunction "OUT_14") (pintype "output"))
      (node (ref "R28") (pin "2") (pinfunction "2_2") (pintype "passive"))
    )
    (net (code "93") (name "Net-(IC6A-IN)") (class "Default")
      (node (ref "IC6") (pin "2") (pinfunction "IN_2") (pintype "input"))
      (node (ref "R89") (pin "2") (pinfunction "2_2") (pintype "passive"))
      (node (ref "R90") (pin "2") (pinfunction "2_2") (pintype "passive"))
    )
    (net (code "94") (name "Net-(IC6B-IN)") (class "Default")
      (node (ref "IC6") (pin "7") (pinfunction "IN_7") (pintype "input"))
      (node (ref "R54") (pin "2") (pinfunction "2_2") (pintype "passive"))
      (node (ref "R56") (pin "2") (pinfunction "2_2") (pintype "passive"))
    )
    (net (code "95") (name "Net-(IC6B-OUT)") (class "Default")
      (node (ref "C16") (pin "2") (pinfunction "2_2") (pintype "passive"))
      (node (ref "IC6") (pin "5") (pinfunction "OUT_5") (pintype "output"))
      (node (ref "IC8") (pin "6") (pinfunction "-IN_6") (pintype "input"))
      (node (ref "R64") (pin "1") (pinfunction "1_1") (pintype "passive"))
    )
    (net (code "96") (name "Net-(IC6C-IN)") (class "Default")
      (node (ref "IC6") (pin "10") (pinfunction "IN_10") (pintype "input"))
      (node (ref "R45") (pin "2") (pinfunction "2_2") (pintype "passive"))
      (node (ref "R47") (pin "2") (pinfunction "2_2") (pintype "passive"))
    )
    (net (code "97") (name "Net-(IC6C-OUT)") (class "Default")
      (node (ref "C14") (pin "2") (pinfunction "2_2") (pintype "passive"))
      (node (ref "IC6") (pin "12") (pinfunction "OUT_12") (pintype "output"))
      (node (ref "IC8") (pin "9") (pinfunction "-IN_9") (pintype "input"))
      (node (ref "R49") (pin "1") (pinfunction "1_1") (pintype "passive"))
    )
    (net (code "98") (name "Net-(IC6D-IN)") (class "Default")
      (node (ref "IC6") (pin "15") (pinfunction "IN_15") (pintype "input"))
      (node (ref "R84") (pin "2") (pinfunction "2_2") (pintype "passive"))
      (node (ref "R85") (pin "2") (pinfunction "2_2") (pintype "passive"))
    )
    (net (code "99") (name "Net-(IC6E-MODE)") (class "Default")
      (node (ref "IC6") (pin "1") (pinfunction "MODE_1") (pintype "input"))
      (node (ref "R110") (pin "1") (pinfunction "1_1") (pintype "passive"))
    )
    (net (code "100") (name "Net-(IC7A-+IN)") (class "Default")
      (node (ref "IC7") (pin "3") (pinfunction "+IN_3") (pintype "input"))
      (node (ref "R32") (pin "2") (pinfunction "2_2") (pintype "passive"))
    )
    (net (code "101") (name "Net-(IC7A--IN)") (class "Default")
      (node (ref "IC7") (pin "1") (pinfunction "OUT_1") (pintype "output"))
      (node (ref "IC7") (pin "2") (pinfunction "-IN_2") (pintype "input"))
      (node (ref "R33") (pin "2") (pinfunction "2_2") (pintype "passive"))
    )
    (net (code "102") (name "Net-(IC7B--IN)") (class "Default")
      (node (ref "IC7") (pin "6") (pinfunction "-IN_6") (pintype "input"))
      (node (ref "R18") (pin "1") (pinfunction "1_1") (pintype "passive"))
      (node (ref "R55") (pin "2") (pinfunction "2_2") (pintype "passive"))
    )
    (net (code "103") (name "Net-(IC7B-OUT)") (class "Default")
      (node (ref "IC7") (pin "7") (pinfunction "OUT_7") (pintype "output"))
      (node (ref "R18") (pin "2") (pinfunction "2_2") (pintype "passive"))
      (node (ref "R58") (pin "2") (pinfunction "2_2") (pintype "passive"))
    )
    (net (code "104") (name "Net-(IC8B-OUT)") (class "Default")
      (node (ref "C16") (pin "1") (pinfunction "1_1") (pintype "passive"))
      (node (ref "IC8") (pin "7") (pinfunction "OUT_7") (pintype "output"))
      (node (ref "R64") (pin "2") (pinfunction "2_2") (pintype "passive"))
      (node (ref "R66") (pin "1") (pinfunction "1_1") (pintype "passive"))
    )
    (net (code "105") (name "Net-(IC8C-OUT)") (class "Default")
      (node (ref "C14") (pin "1") (pinfunction "1_1") (pintype "passive"))
      (node (ref "IC8") (pin "8") (pinfunction "OUT_8") (pintype "output"))
      (node (ref "R49") (pin "2") (pinfunction "2_2") (pintype "passive"))
      (node (ref "R68") (pin "1") (pinfunction "1_1") (pintype "passive"))
    )
    (net (code "106") (name "Net-(IC8D--IN)") (class "Default")
      (node (ref "IC8") (pin "13") (pinfunction "-IN_13") (pintype "input"))
      (node (ref "R116") (pin "1") (pinfunction "1_1") (pintype "passive"))
      (node (ref "R67") (pin "1") (pinfunction "1_1") (pintype "passive"))
      (node (ref "R68") (pin "2") (pinfunction "2_2") (pintype "passive"))
    )
    (net (code "107") (name "Net-(IC8D-OUT)") (class "Default")
      (node (ref "1K1") (pin "1") (pinfunction "1_1") (pintype "passive"))
      (node (ref "IC8") (pin "14") (pinfunction "OUT_14") (pintype "output"))
      (node (ref "R67") (pin "2") (pinfunction "2_2") (pintype "passive"))
    )
    (net (code "108") (name "Net-(IC9A-+IN)") (class "Default")
      (node (ref "IC9") (pin "3") (pinfunction "+IN_3") (pintype "input"))
      (node (ref "R72") (pin "2") (pinfunction "2_2") (pintype "passive"))
    )
    (net (code "109") (name "Net-(IC9A--IN)") (class "Default")
      (node (ref "IC9") (pin "1") (pinfunction "OUT_1") (pintype "output"))
      (node (ref "IC9") (pin "2") (pinfunction "-IN_2") (pintype "input"))
      (node (ref "R78") (pin "1") (pinfunction "1_1") (pintype "passive"))
      (node (ref "R80") (pin "1") (pinfunction "1_1") (pintype "passive"))
    )
    (net (code "110") (name "Net-(IC9B-+IN)") (class "Default")
      (node (ref "IC9") (pin "5") (pinfunction "+IN_5") (pintype "input"))
      (node (ref "R74") (pin "2") (pinfunction "2_2") (pintype "passive"))
    )
    (net (code "111") (name "Net-(IC9B--IN)") (class "Default")
      (node (ref "IC9") (pin "6") (pinfunction "-IN_6") (pintype "input"))
      (node (ref "IC9") (pin "7") (pinfunction "OUT_7") (pintype "output"))
      (node (ref "R75") (pin "1") (pinfunction "1_1") (pintype "passive"))
      (node (ref "R77") (pin "1") (pinfunction "1_1") (pintype "passive"))
    )
    (net (code "112") (name "Net-(IC9C--IN)") (class "Default")
      (node (ref "IC9") (pin "9") (pinfunction "-IN_9") (pintype "input"))
      (node (ref "R73") (pin "2") (pinfunction "2_2") (pintype "passive"))
      (node (ref "R78") (pin "2") (pinfunction "2_2") (pintype "passive"))
      (node (ref "R79") (pin "1") (pinfunction "1_1") (pintype "passive"))
      (node (ref "R81") (pin "1") (pinfunction "1_1") (pintype "passive"))
    )
    (net (code "113") (name "Net-(IC9D--IN)") (class "Default")
      (node (ref "IC9") (pin "13") (pinfunction "-IN_13") (pintype "input"))
      (node (ref "R75") (pin "2") (pinfunction "2_2") (pintype "passive"))
      (node (ref "R76") (pin "1") (pinfunction "1_1") (pintype "passive"))
      (node (ref "R82") (pin "1") (pinfunction "1_1") (pintype "passive"))
    )
    (net (code "114") (name "Net-(IC10A-+IN)") (class "Default")
      (node (ref "IC10") (pin "3") (pinfunction "+IN_3") (pintype "input"))
      (node (ref "R16") (pin "2") (pinfunction "2_2") (pintype "passive"))
    )
    (net (code "115") (name "Net-(IC10A--IN)") (class "Default")
      (node (ref "IC10") (pin "1") (pinfunction "OUT_1") (pintype "output"))
      (node (ref "IC10") (pin "2") (pinfunction "-IN_2") (pintype "input"))
      (node (ref "R83") (pin "2") (pinfunction "2_2") (pintype "passive"))
    )
    (net (code "116") (name "Net-(IC10B--IN)") (class "Default")
      (node (ref "IC10") (pin "6") (pinfunction "-IN_6") (pintype "input"))
      (node (ref "R87") (pin "2") (pinfunction "2_2") (pintype "passive"))
      (node (ref "R92") (pin "1") (pinfunction "1_1") (pintype "passive"))
    )
    (net (code "117") (name "Net-(IC10B-OUT)") (class "Default")
      (node (ref "IC10") (pin "7") (pinfunction "OUT_7") (pintype "output"))
      (node (ref "R88") (pin "2") (pinfunction "2_2") (pintype "passive"))
      (node (ref "R92") (pin "2") (pinfunction "2_2") (pintype "passive"))
    )
    (net (code "118") (name "Net-(IC11A-+IN)") (class "Default")
      (node (ref "C1") (pin "1") (pinfunction "1_1") (pintype "passive"))
      (node (ref "IC11") (pin "3") (pinfunction "+IN_3") (pintype "input"))
      (node (ref "OFFSET_LINA") (pin "2") (pinfunction "S_2") (pintype "passive"))
    )
    (net (code "119") (name "Net-(IC11B-+IN)") (class "Default")
      (node (ref "C20") (pin "1") (pinfunction "1_1") (pintype "passive"))
      (node (ref "IC11") (pin "5") (pinfunction "+IN_5") (pintype "input"))
      (node (ref "OFFSET_LINB") (pin "2") (pinfunction "S_2") (pintype "passive"))
    )
    (net (code "120") (name "Net-(IC12A--IN)") (class "Default")
      (node (ref "IC12") (pin "2") (pinfunction "-IN_2") (pintype "input"))
      (node (ref "R100") (pin "2") (pinfunction "2_2") (pintype "passive"))
      (node (ref "R101") (pin "1") (pinfunction "1_1") (pintype "passive"))
    )
    (net (code "121") (name "Net-(IC12A-OUT)") (class "Default")
      (node (ref "IC12") (pin "1") (pinfunction "OUT_1") (pintype "output"))
      (node (ref "R100") (pin "1") (pinfunction "1_1") (pintype "passive"))
      (node (ref "R102") (pin "2") (pinfunction "2_2") (pintype "passive"))
    )
    (net (code "122") (name "Net-(IC12B--IN)") (class "Default")
      (node (ref "IC12") (pin "6") (pinfunction "-IN_6") (pintype "input"))
      (node (ref "R102") (pin "1") (pinfunction "1_1") (pintype "passive"))
      (node (ref "R99") (pin "2") (pinfunction "2_2") (pintype "passive"))
    )
    (net (code "123") (name "Net-(IC12B-OUT)") (class "Default")
      (node (ref "IC12") (pin "7") (pinfunction "OUT_7") (pintype "output"))
      (node (ref "R97") (pin "1") (pinfunction "1_1") (pintype "passive"))
      (node (ref "R99") (pin "1") (pinfunction "1_1") (pintype "passive"))
    )
    (net (code "124") (name "Net-(IC12C--IN)") (class "Default")
      (node (ref "IC12") (pin "9") (pinfunction "-IN_9") (pintype "input"))
      (node (ref "R107") (pin "1") (pinfunction "1_1") (pintype "passive"))
      (node (ref "R108") (pin "2") (pinfunction "2_2") (pintype "passive"))
    )
    (net (code "125") (name "Net-(IC12C-OUT)") (class "Default")
      (node (ref "IC12") (pin "8") (pinfunction "OUT_8") (pintype "output"))
      (node (ref "R103") (pin "1") (pinfunction "1_1") (pintype "passive"))
      (node (ref "R108") (pin "1") (pinfunction "1_1") (pintype "passive"))
    )
    (net (code "126") (name "Net-(IC12D-+IN)") (class "Default")
      (node (ref "C24") (pin "1") (pinfunction "1_1") (pintype "passive"))
      (node (ref "IC12") (pin "12") (pinfunction "+IN_12") (pintype "input"))
      (node (ref "OFFSET_REFB") (pin "2") (pinfunction "S_2") (pintype "passive"))
    )
    (net (code "127") (name "Net-(IC14A--IN)") (class "Default")
      (node (ref "IC14") (pin "2") (pinfunction "-IN_2") (pintype "input"))
      (node (ref "R39") (pin "2") (pinfunction "2_2") (pintype "passive"))
      (node (ref "R42") (pin "1") (pinfunction "1_1") (pintype "passive"))
    )
    (net (code "128") (name "Net-(IC14A-OUT)") (class "Default")
      (node (ref "IC14") (pin "1") (pinfunction "OUT_1") (pintype "output"))
      (node (ref "R15") (pin "2") (pinfunction "2_2") (pintype "passive"))
      (node (ref "R39") (pin "1") (pinfunction "1_1") (pintype "passive"))
    )
    (net (code "129") (name "Net-(IC14B-+IN)") (class "Default")
      (node (ref "IC14") (pin "5") (pinfunction "+IN_5") (pintype "input"))
      (node (ref "R17") (pin "1") (pinfunction "1_1") (pintype "passive"))
      (node (ref "R25") (pin "2") (pinfunction "2_2") (pintype "passive"))
    )
    (net (code "130") (name "Net-(IC14B--IN)") (class "Default")
      (node (ref "IC14") (pin "6") (pinfunction "-IN_6") (pintype "input"))
      (node (ref "R15") (pin "1") (pinfunction "1_1") (pintype "passive"))
      (node (ref "R38") (pin "2") (pinfunction "2_2") (pintype "passive"))
    )
    (net (code "131") (name "Net-(IC14C--IN)") (class "Default")
      (node (ref "IC14") (pin "9") (pinfunction "-IN_9") (pintype "input"))
      (node (ref "R40") (pin "1") (pinfunction "1_1") (pintype "passive"))
      (node (ref "R41") (pin "2") (pinfunction "2_2") (pintype "passive"))
    )
    (net (code "132") (name "Net-(IC14C-OUT)") (class "Default")
      (node (ref "IC14") (pin "8") (pinfunction "OUT_8") (pintype "output"))
      (node (ref "R19") (pin "1") (pinfunction "1_1") (pintype "passive"))
      (node (ref "R41") (pin "1") (pinfunction "1_1") (pintype "passive"))
    )
    (net (code "133") (name "Net-(IC14D-+IN)") (class "Default")
      (node (ref "C9") (pin "1") (pinfunction "1_1") (pintype "passive"))
      (node (ref "IC14") (pin "12") (pinfunction "+IN_12") (pintype "input"))
      (node (ref "OFFSET_REF") (pin "2") (pinfunction "S_2") (pintype "passive"))
    )
    (net (code "134") (name "Net-(OFFSET_LINA-E)") (class "Default")
      (node (ref "OFFSET_LINA") (pin "3") (pinfunction "E_3") (pintype "passive"))
      (node (ref "R13") (pin "1") (pinfunction "1_1") (pintype "passive"))
    )
    (net (code "135") (name "Net-(OFFSET_LINB-E)") (class "Default")
      (node (ref "OFFSET_LINB") (pin "3") (pinfunction "E_3") (pintype "passive"))
      (node (ref "R93") (pin "1") (pinfunction "1_1") (pintype "passive"))
    )
    (net (code "136") (name "Net-(OFFSET_REF-E)") (class "Default")
      (node (ref "OFFSET_REF") (pin "3") (pinfunction "E_3") (pintype "passive"))
      (node (ref "R2") (pin "1") (pinfunction "1_1") (pintype "passive"))
    )
    (net (code "137") (name "Net-(OFFSET_REFB-E)") (class "Default")
      (node (ref "OFFSET_REFB") (pin "3") (pinfunction "E_3") (pintype "passive"))
      (node (ref "R106") (pin "1") (pinfunction "1_1") (pintype "passive"))
    )
    (net (code "138") (name "Net-(Q1-PadB)") (class "Default")
      (node (ref "Q1") (pin "B") (pinfunction "B_B") (pintype "passive"))
      (node (ref "R113") (pin "2") (pinfunction "2_2") (pintype "passive"))
      (node (ref "R115") (pin "2") (pinfunction "2_2") (pintype "passive"))
    )
    (net (code "139") (name "Net-(Q2-PadB)") (class "Default")
      (node (ref "Q2") (pin "B") (pinfunction "B_B") (pintype "passive"))
      (node (ref "R123") (pin "2") (pinfunction "2_2") (pintype "passive"))
      (node (ref "R125") (pin "2") (pinfunction "2_2") (pintype "passive"))
    )
    (net (code "140") (name "Net-(Q3-PadB)") (class "Default")
      (node (ref "Q3") (pin "B") (pinfunction "B_B") (pintype "passive"))
      (node (ref "R126") (pin "2") (pinfunction "2_2") (pintype "passive"))
      (node (ref "R128") (pin "2") (pinfunction "2_2") (pintype "passive"))
    )
    (net (code "141") (name "Net-(Q5-PadB)") (class "Default")
      (node (ref "Q5") (pin "B") (pinfunction "B_B") (pintype "passive"))
      (node (ref "R111") (pin "2") (pinfunction "2_2") (pintype "passive"))
      (node (ref "R116") (pin "2") (pinfunction "2_2") (pintype "passive"))
    )
    (net (code "142") (name "Net-(Q9-D)") (class "Default")
      (node (ref "JP8") (pin "1") (pinfunction "1_1") (pintype "passive"))
      (node (ref "JP8") (pin "2") (pinfunction "2_2") (pintype "passive"))
      (node (ref "Q9") (pin "3") (pinfunction "D_3") (pintype "passive"))
    )
    (net (code "143") (name "Net-(Q10-D)") (class "Default")
      (node (ref "JP8") (pin "10") (pinfunction "10_10") (pintype "passive"))
      (node (ref "JP8") (pin "9") (pinfunction "9_9") (pintype "passive"))
      (node (ref "Q10") (pin "3") (pinfunction "D_3") (pintype "passive"))
    )
    (net (code "144") (name "Net-(R5-Pad1)") (class "Default")
      (node (ref "R5") (pin "1") (pinfunction "1_1") (pintype "passive"))
      (node (ref "R9") (pin "2") (pinfunction "2_2") (pintype "passive"))
    )
    (net (code "145") (name "Net-(R24-Pad2)") (class "Default")
      (node (ref "R24") (pin "2") (pinfunction "2_2") (pintype "passive"))
      (node (ref "R7") (pin "1") (pinfunction "1_1") (pintype "passive"))
    )
    (net (code "146") (name "Net-(R45-Pad1)") (class "Default")
      (node (ref "R45") (pin "1") (pinfunction "1_1") (pintype "passive"))
      (node (ref "R48") (pin "2") (pinfunction "2_2") (pintype "passive"))
    )
    (net (code "147") (name "Net-(R54-Pad1)") (class "Default")
      (node (ref "R54") (pin "1") (pinfunction "1_1") (pintype "passive"))
      (node (ref "R57") (pin "2") (pinfunction "2_2") (pintype "passive"))
    )
    (net (code "148") (name "OFFSET_LIN_A") (class "Default")
      (node (ref "IC11") (pin "1") (pinfunction "OUT_1") (pintype "output"))
      (node (ref "IC11") (pin "2") (pinfunction "-IN_2") (pintype "input"))
      (node (ref "IC7") (pin "10") (pinfunction "+IN_10") (pintype "input"))
      (node (ref "IC7") (pin "12") (pinfunction "+IN_12") (pintype "input"))
    )
    (net (code "149") (name "OFFSET_LIN_B") (class "Default")
      (node (ref "IC10") (pin "10") (pinfunction "+IN_10") (pintype "input"))
      (node (ref "IC10") (pin "12") (pinfunction "+IN_12") (pintype "input"))
      (node (ref "IC11") (pin "6") (pinfunction "-IN_6") (pintype "input"))
      (node (ref "IC11") (pin "7") (pinfunction "OUT_7") (pintype "output"))
    )
    (net (code "150") (name "OFFSET_REF") (class "Default")
      (node (ref "IC14") (pin "10") (pinfunction "+IN_10") (pintype "input"))
      (node (ref "IC14") (pin "13") (pinfunction "-IN_13") (pintype "input"))
      (node (ref "IC14") (pin "14") (pinfunction "OUT_14") (pintype "output"))
      (node (ref "R25") (pin "1") (pinfunction "1_1") (pintype "passive"))
    )
    (net (code "151") (name "OFFSET_REF_B") (class "Default")
      (node (ref "IC12") (pin "10") (pinfunction "+IN_10") (pintype "input"))
      (node (ref "IC12") (pin "13") (pinfunction "-IN_13") (pintype "input"))
      (node (ref "IC12") (pin "14") (pinfunction "OUT_14") (pintype "output"))
      (node (ref "IC12") (pin "5") (pinfunction "+IN_5") (pintype "input"))
    )
    (net (code "152") (name "OUT_A") (class "Default")
      (node (ref "1K") (pin "2") (pinfunction "2_2") (pintype "passive"))
      (node (ref "J2") (pin "1") (pinfunction "1_1") (pintype "passive"))
      (node (ref "JP7") (pin "7") (pinfunction "7_7") (pintype "passive"))
      (node (ref "OUT_A") (pin "P$3") (pinfunction "3_P$3") (pintype "passive"))
    )
    (net (code "153") (name "OUT_A+") (class "Default")
      (node (ref "JP7") (pin "5") (pinfunction "5_5") (pintype "passive"))
    )
    (net (code "154") (name "OUT_A-") (class "Default")
      (node (ref "JP7") (pin "6") (pinfunction "6_6") (pintype "passive"))
    )
    (net (code "155") (name "OUT_B") (class "Default")
      (node (ref "1K1") (pin "2") (pinfunction "2_2") (pintype "passive"))
      (node (ref "J2") (pin "5") (pinfunction "5_5") (pintype "passive"))
      (node (ref "JP7") (pin "3") (pinfunction "3_3") (pintype "passive"))
      (node (ref "OUT_B") (pin "P$3") (pinfunction "3_P$3") (pintype "passive"))
    )
    (net (code "156") (name "POT_EXPA_1") (class "Default")
      (node (ref "IC1") (pin "12") (pinfunction "+IN_12") (pintype "input"))
      (node (ref "JP2") (pin "4") (pinfunction "4_4") (pintype "passive"))
      (node (ref "JP3") (pin "4") (pinfunction "4_4") (pintype "passive"))
      (node (ref "POT_EXPA") (pin "1") (pinfunction "1_1") (pintype "bidirectional"))
      (node (ref "R22") (pin "2") (pinfunction "2_2") (pintype "passive"))
    )
    (net (code "157") (name "POT_EXPA_3") (class "Default")
      (node (ref "JP2") (pin "3") (pinfunction "3_3") (pintype "passive"))
      (node (ref "JP3") (pin "3") (pinfunction "3_3") (pintype "passive"))
      (node (ref "POT_EXPA") (pin "3") (pinfunction "3_3") (pintype "bidirectional"))
      (node (ref "R14") (pin "2") (pinfunction "2_2") (pintype "passive"))
    )
    (net (code "158") (name "POT_EXPB_1") (class "Default")
      (node (ref "IC9") (pin "12") (pinfunction "+IN_12") (pintype "input"))
      (node (ref "JP2") (pin "2") (pinfunction "2_2") (pintype "passive"))
      (node (ref "JP3") (pin "2") (pinfunction "2_2") (pintype "passive"))
      (node (ref "POT_EXPB") (pin "1") (pinfunction "1_1") (pintype "bidirectional"))
      (node (ref "R77") (pin "2") (pinfunction "2_2") (pintype "passive"))
    )
    (net (code "159") (name "POT_EXPB_3") (class "Default")
      (node (ref "JP2") (pin "1") (pinfunction "1_1") (pintype "passive"))
      (node (ref "JP3") (pin "1") (pinfunction "1_1") (pintype "passive"))
      (node (ref "POT_EXPB") (pin "3") (pinfunction "3_3") (pintype "bidirectional"))
      (node (ref "R82") (pin "2") (pinfunction "2_2") (pintype "passive"))
    )
    (net (code "160") (name "POT_LINA_1") (class "Default")
      (node (ref "IC1") (pin "10") (pinfunction "+IN_10") (pintype "input"))
      (node (ref "JP3") (pin "9") (pinfunction "9_9") (pintype "passive"))
      (node (ref "POT_LINA") (pin "1") (pinfunction "1_1") (pintype "bidirectional"))
      (node (ref "R12") (pin "2") (pinfunction "2_2") (pintype "passive"))
    )
    (net (code "161") (name "POT_LINA_3") (class "Default")
      (node (ref "JP2") (pin "8") (pinfunction "8_8") (pintype "passive"))
      (node (ref "JP3") (pin "8") (pinfunction "8_8") (pintype "passive"))
      (node (ref "POT_LINA") (pin "3") (pinfunction "3_3") (pintype "bidirectional"))
      (node (ref "R8") (pin "2") (pinfunction "2_2") (pintype "passive"))
    )
    (net (code "162") (name "POT_LINB_1") (class "Default")
      (node (ref "IC9") (pin "10") (pinfunction "+IN_10") (pintype "input"))
      (node (ref "JP2") (pin "7") (pinfunction "7_7") (pintype "passive"))
      (node (ref "JP2") (pin "9") (pinfunction "9_9") (pintype "passive"))
      (node (ref "JP3") (pin "7") (pinfunction "7_7") (pintype "passive"))
      (node (ref "POT_LINB") (pin "1") (pinfunction "1_1") (pintype "bidirectional"))
      (node (ref "R80") (pin "2") (pinfunction "2_2") (pintype "passive"))
    )
    (net (code "163") (name "POT_LINB_3") (class "Default")
      (node (ref "JP2") (pin "6") (pinfunction "6_6") (pintype "passive"))
      (node (ref "JP3") (pin "6") (pinfunction "6_6") (pintype "passive"))
      (node (ref "POT_LINB") (pin "3") (pinfunction "3_3") (pintype "bidirectional"))
      (node (ref "R81") (pin "2") (pinfunction "2_2") (pintype "passive"))
    )
    (net (code "164") (name "UNIPOLAR_A") (class "Default")
      (node (ref "JP10") (pin "3") (pinfunction "3_3") (pintype "passive"))
      (node (ref "JP9") (pin "3") (pinfunction "3_3") (pintype "passive"))
      (node (ref "R119") (pin "1") (pinfunction "1_1") (pintype "passive"))
      (node (ref "S1") (pin "3") (pinfunction "S_3") (pintype "passive"))
    )
    (net (code "165") (name "UNIPOLAR_B") (class "Default")
      (node (ref "JP10") (pin "1") (pinfunction "1_1") (pintype "passive"))
      (node (ref "JP9") (pin "1") (pinfunction "1_1") (pintype "passive"))
      (node (ref "R120") (pin "1") (pinfunction "1_1") (pintype "passive"))
      (node (ref "S2") (pin "3") (pinfunction "S_3") (pintype "passive"))
    )
    (net (code "166") (name "unconnected-(S1-O-Pad1)") (class "Default")
      (node (ref "S1") (pin "1") (pinfunction "O_1") (pintype "passive"))
    )
    (net (code "167") (name "unconnected-(S2-O-Pad1)") (class "Default")
      (node (ref "S2") (pin "1") (pinfunction "O_1") (pintype "passive"))
    )
  )
)
